# mcat-4cu-b-v2c.net
KiCad netlist of a schematic drawn in EAGLE
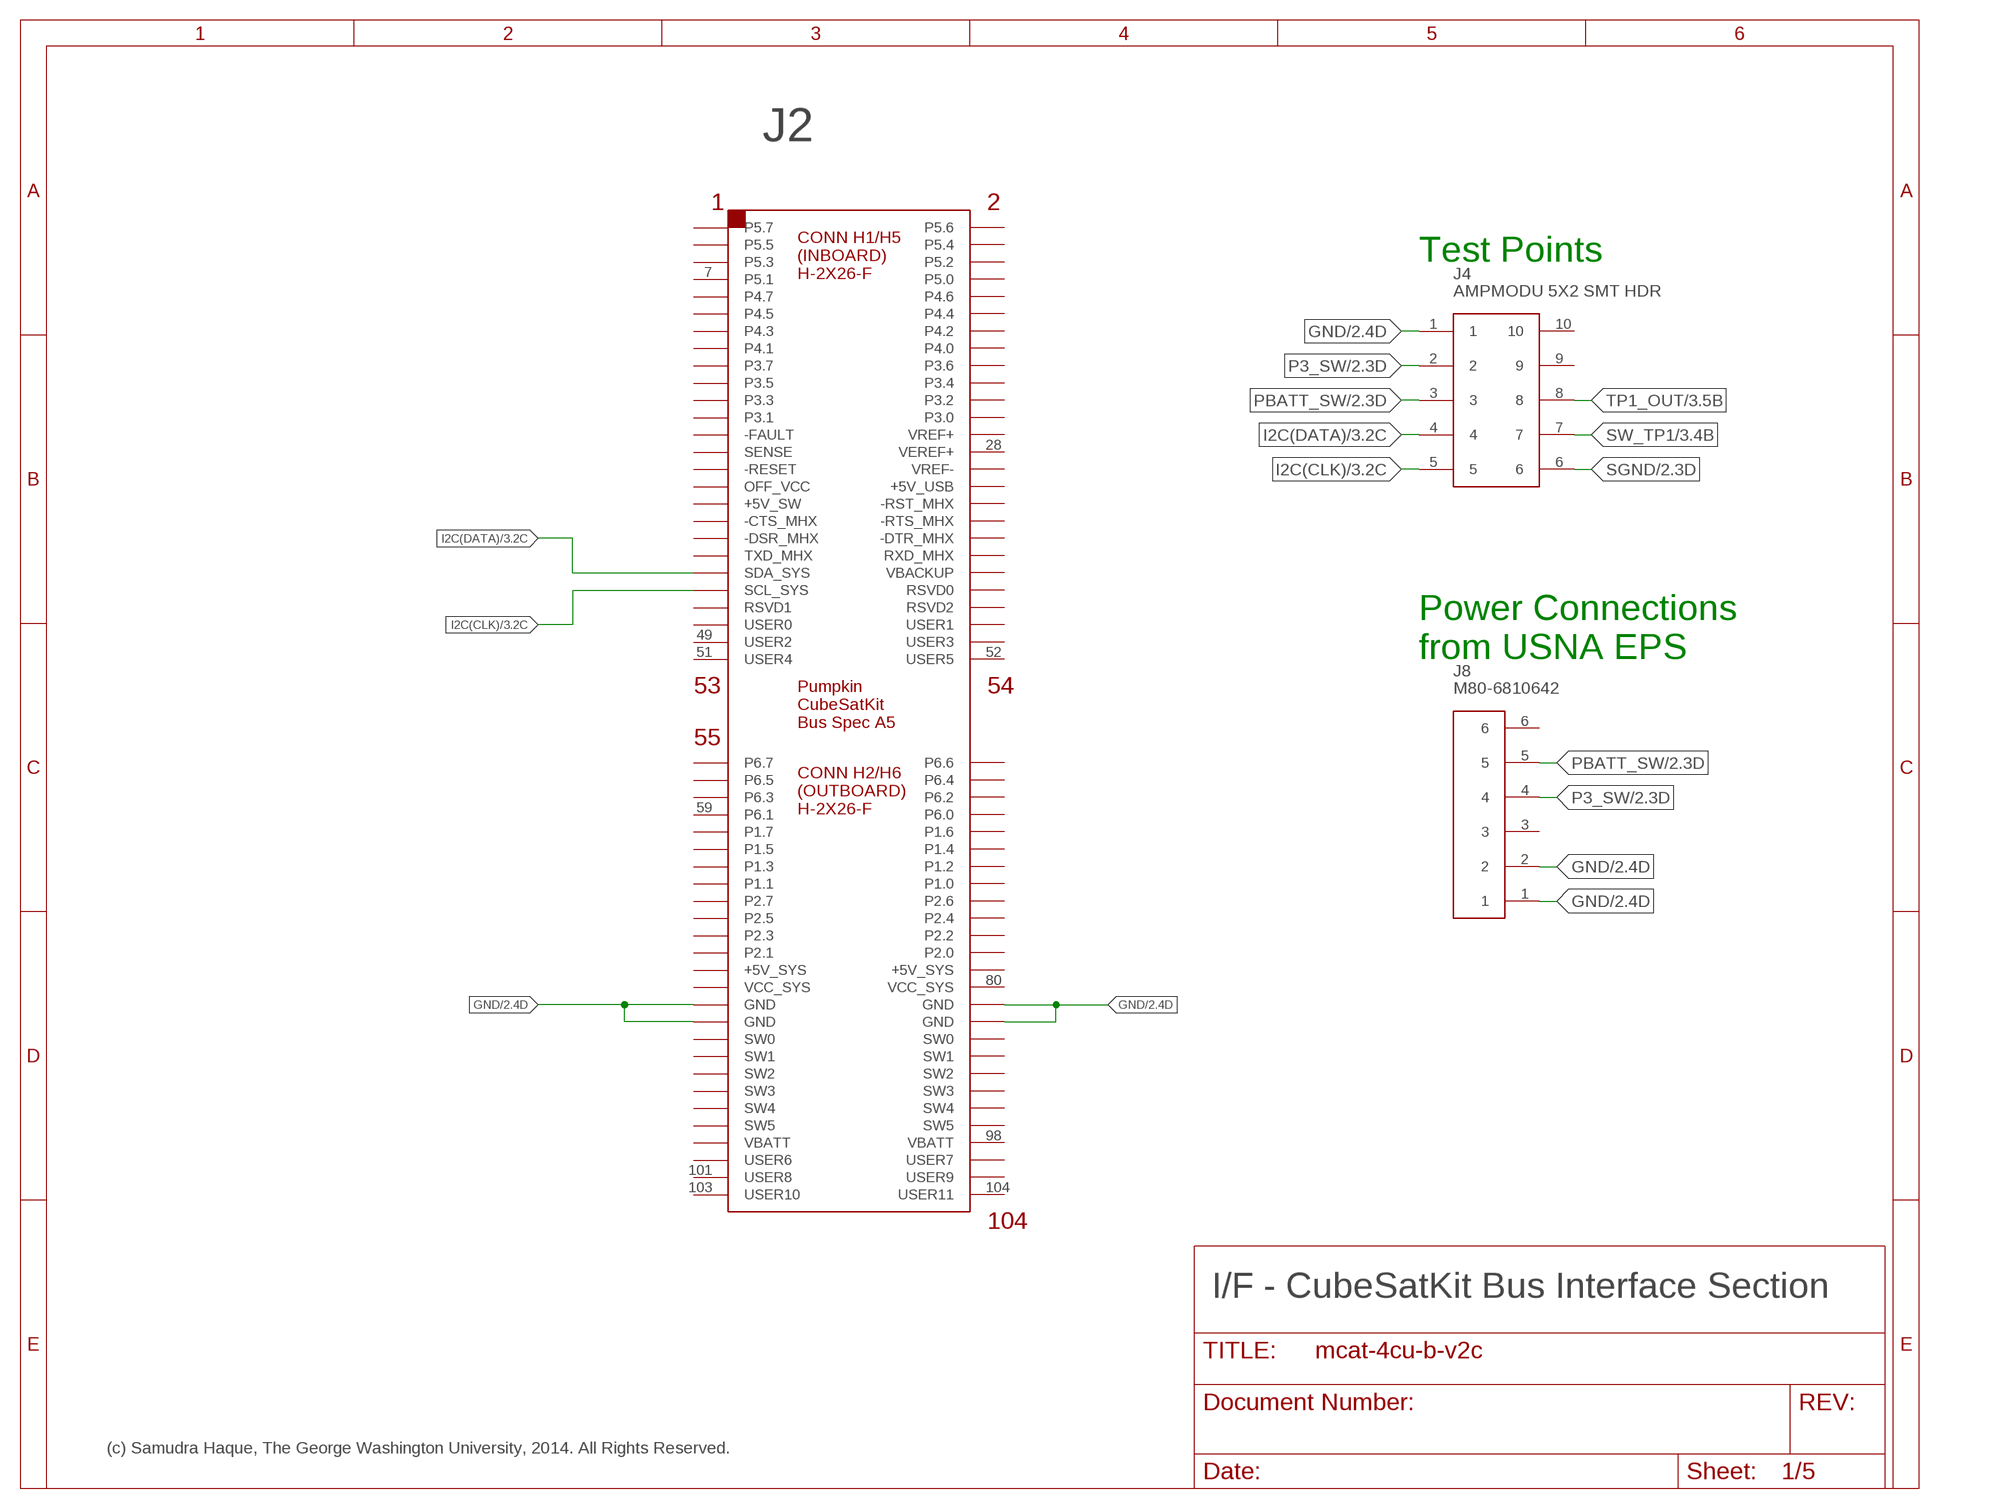
[diagram p0: schematic, sheet 1]
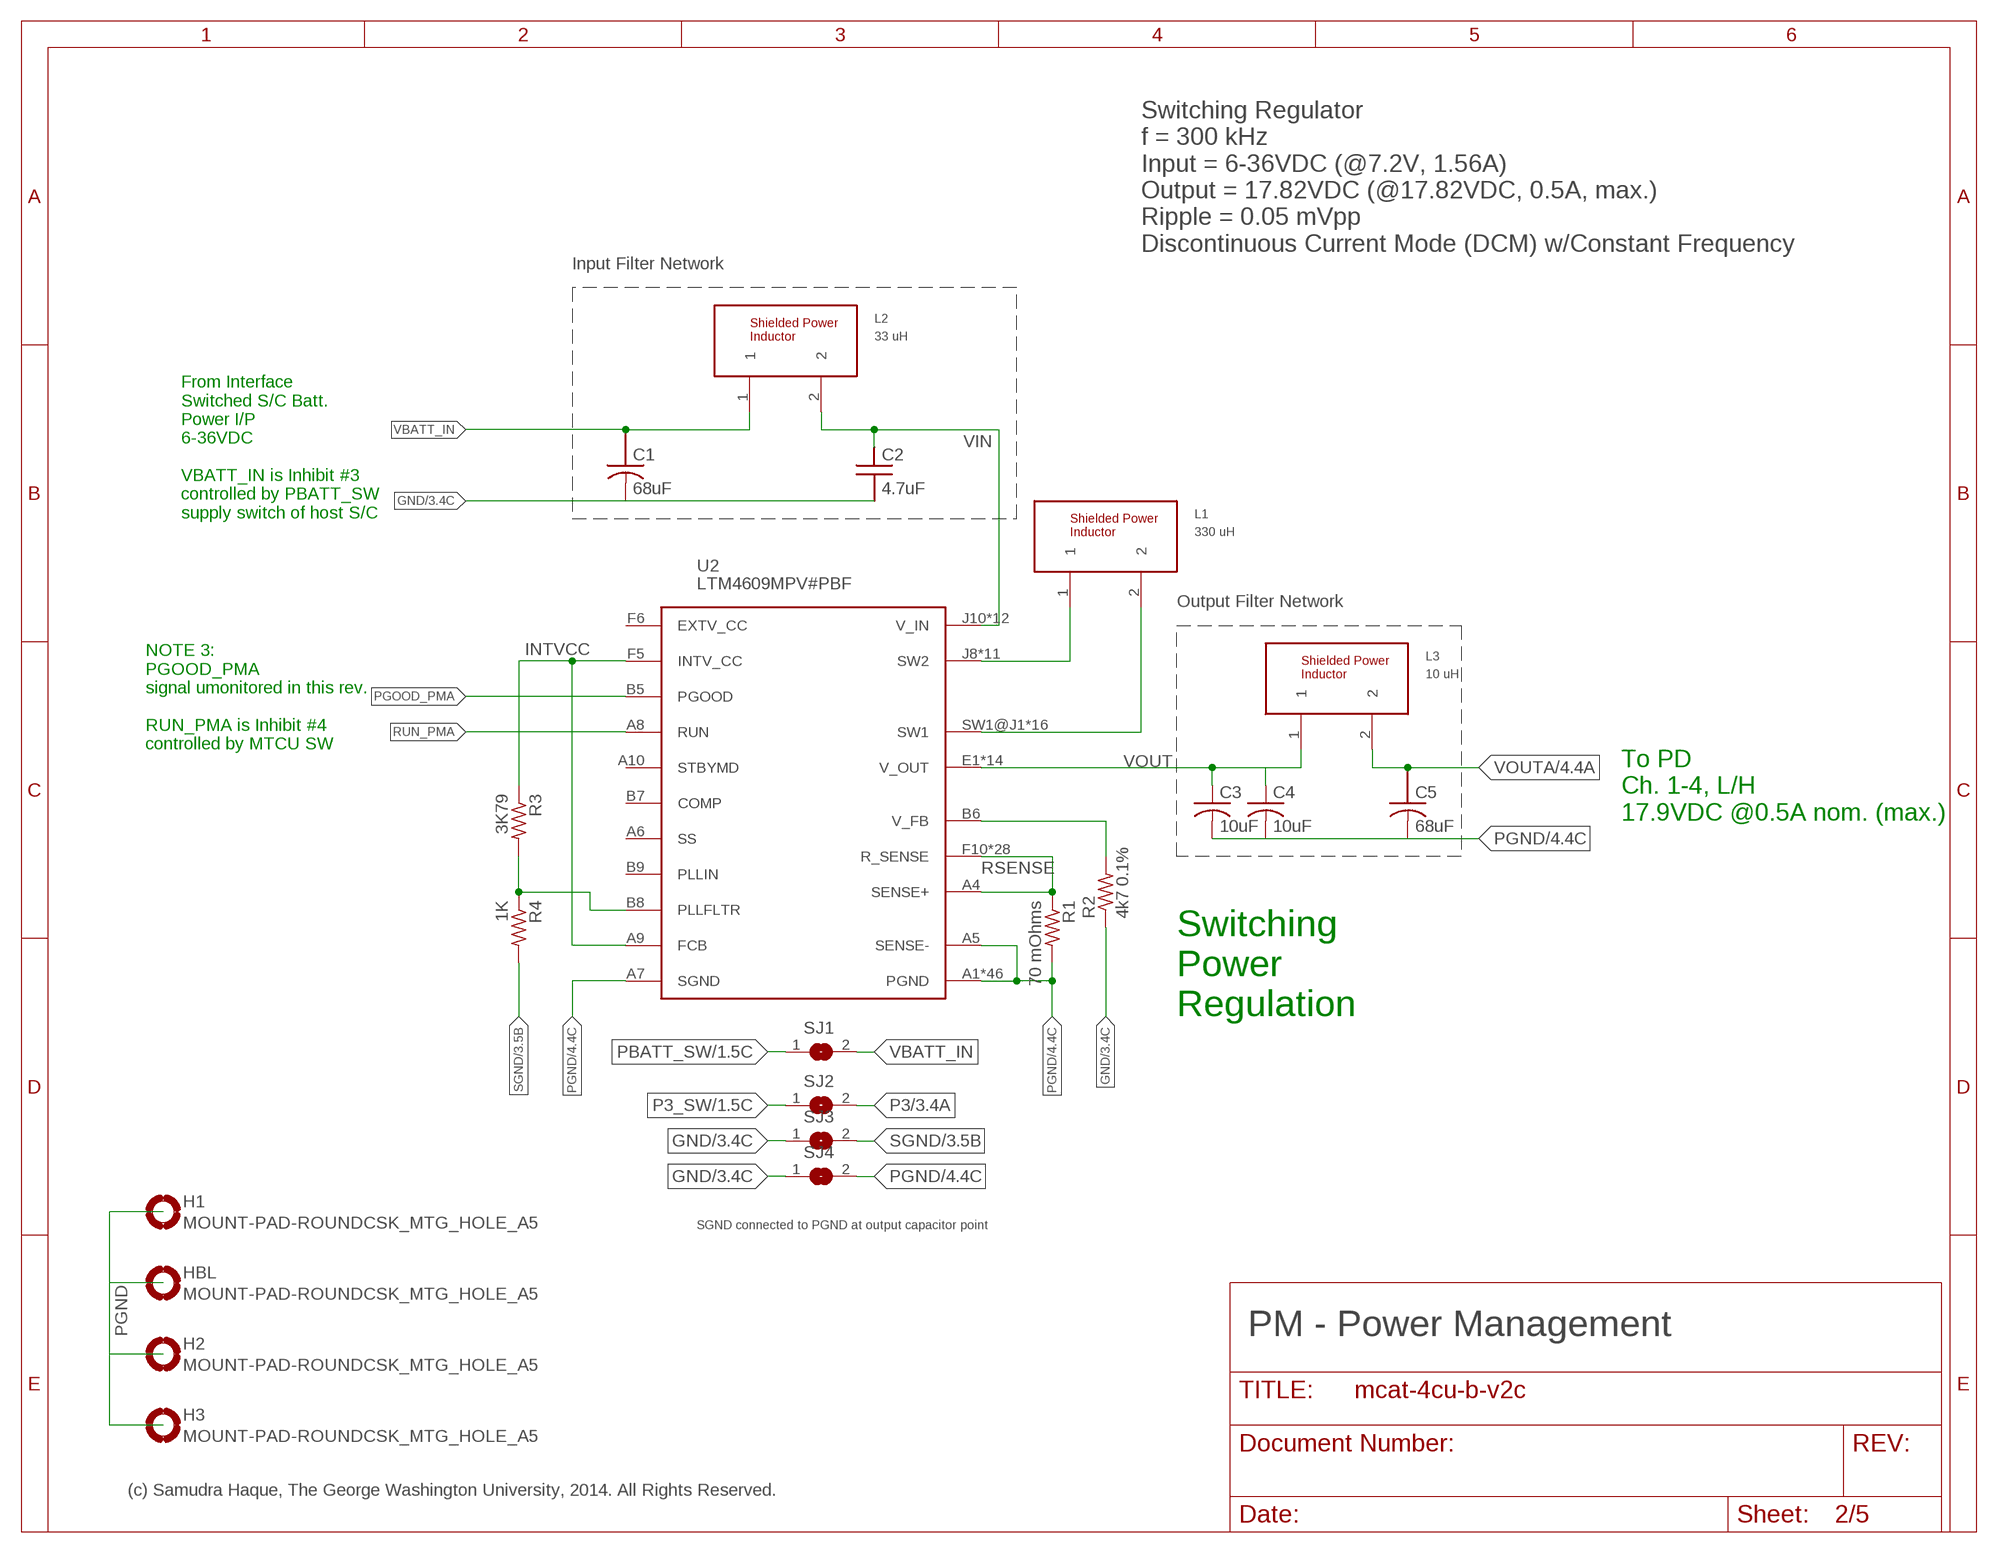
[diagram p1: schematic, sheet 2]
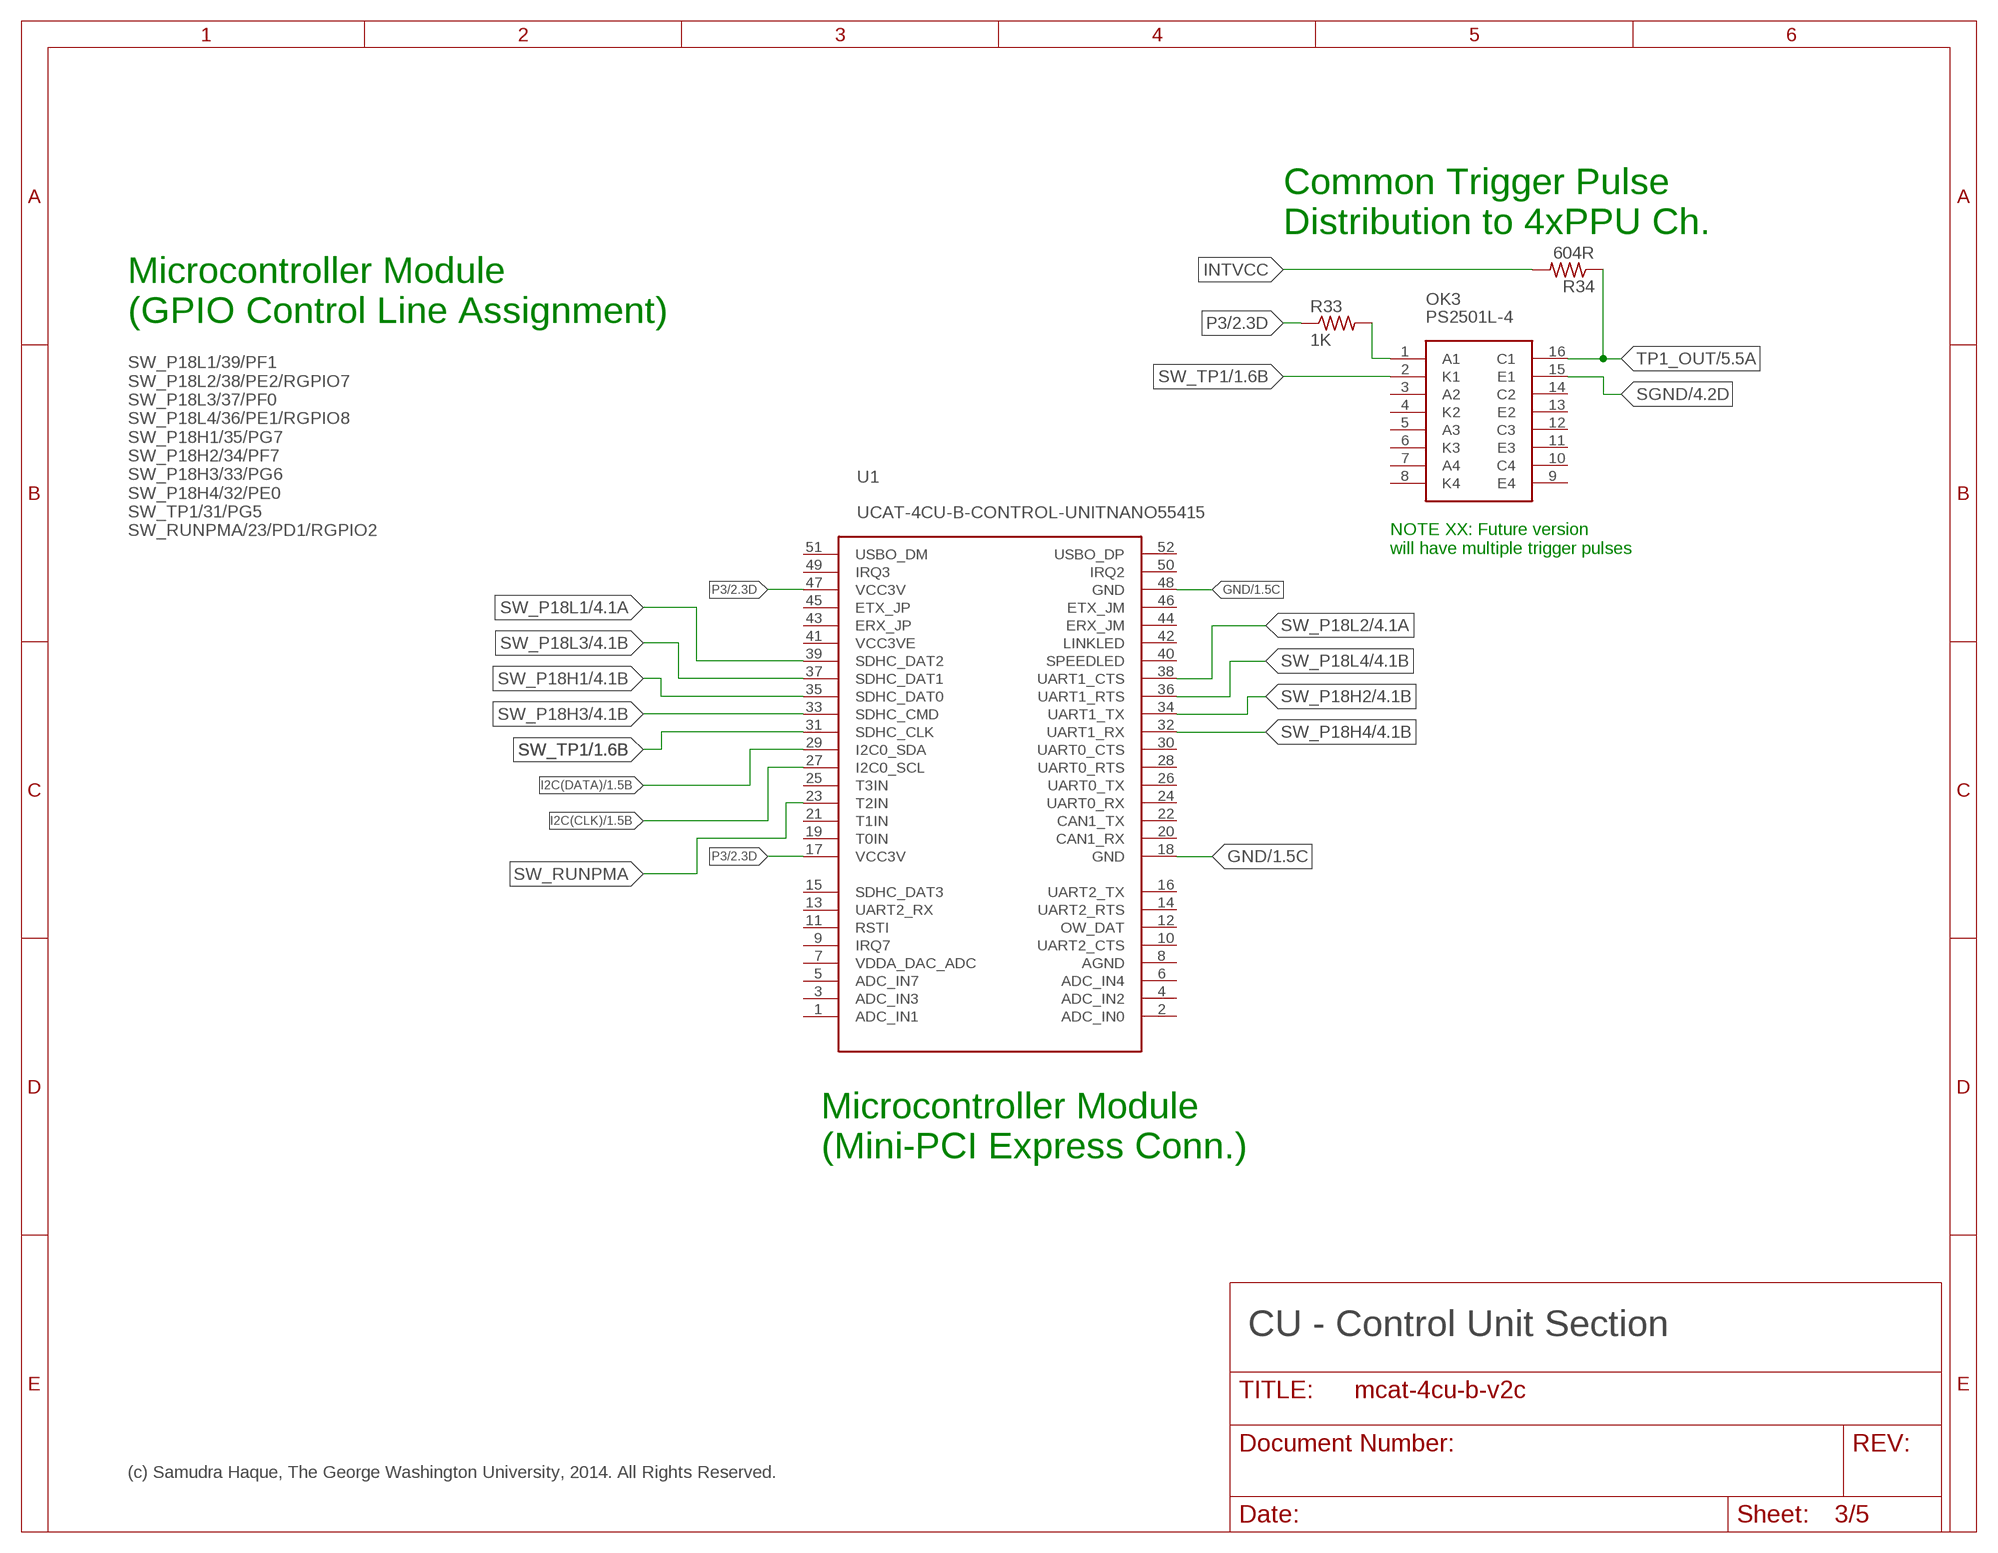
[diagram p2: schematic, sheet 3]
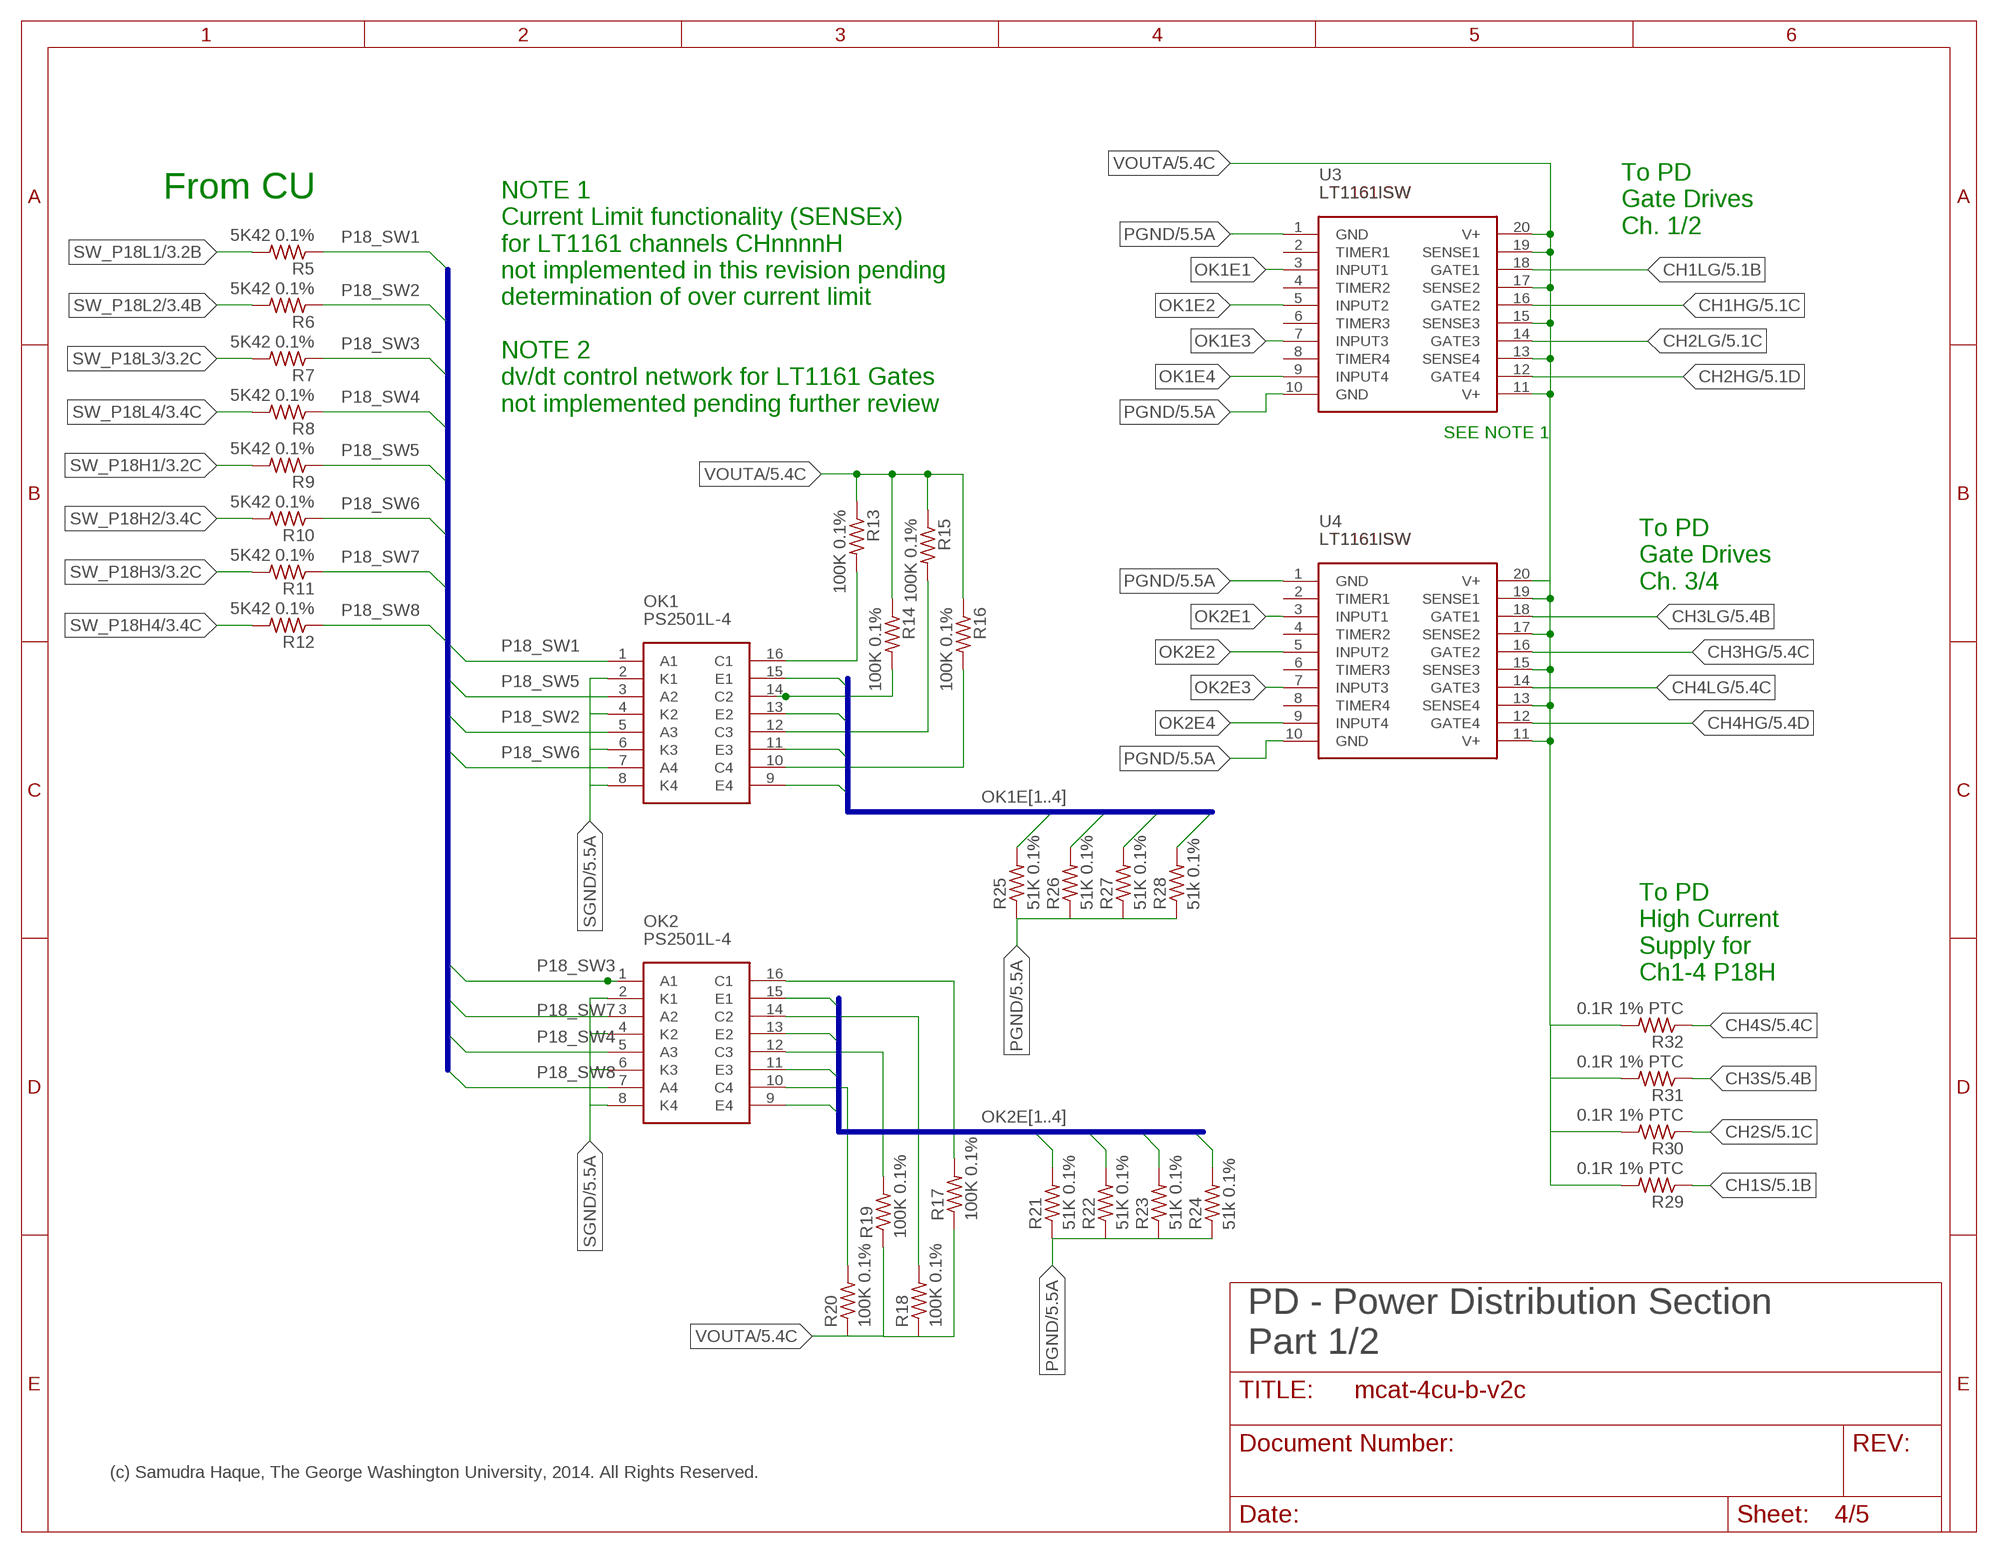
[diagram p3: schematic, sheet 4]
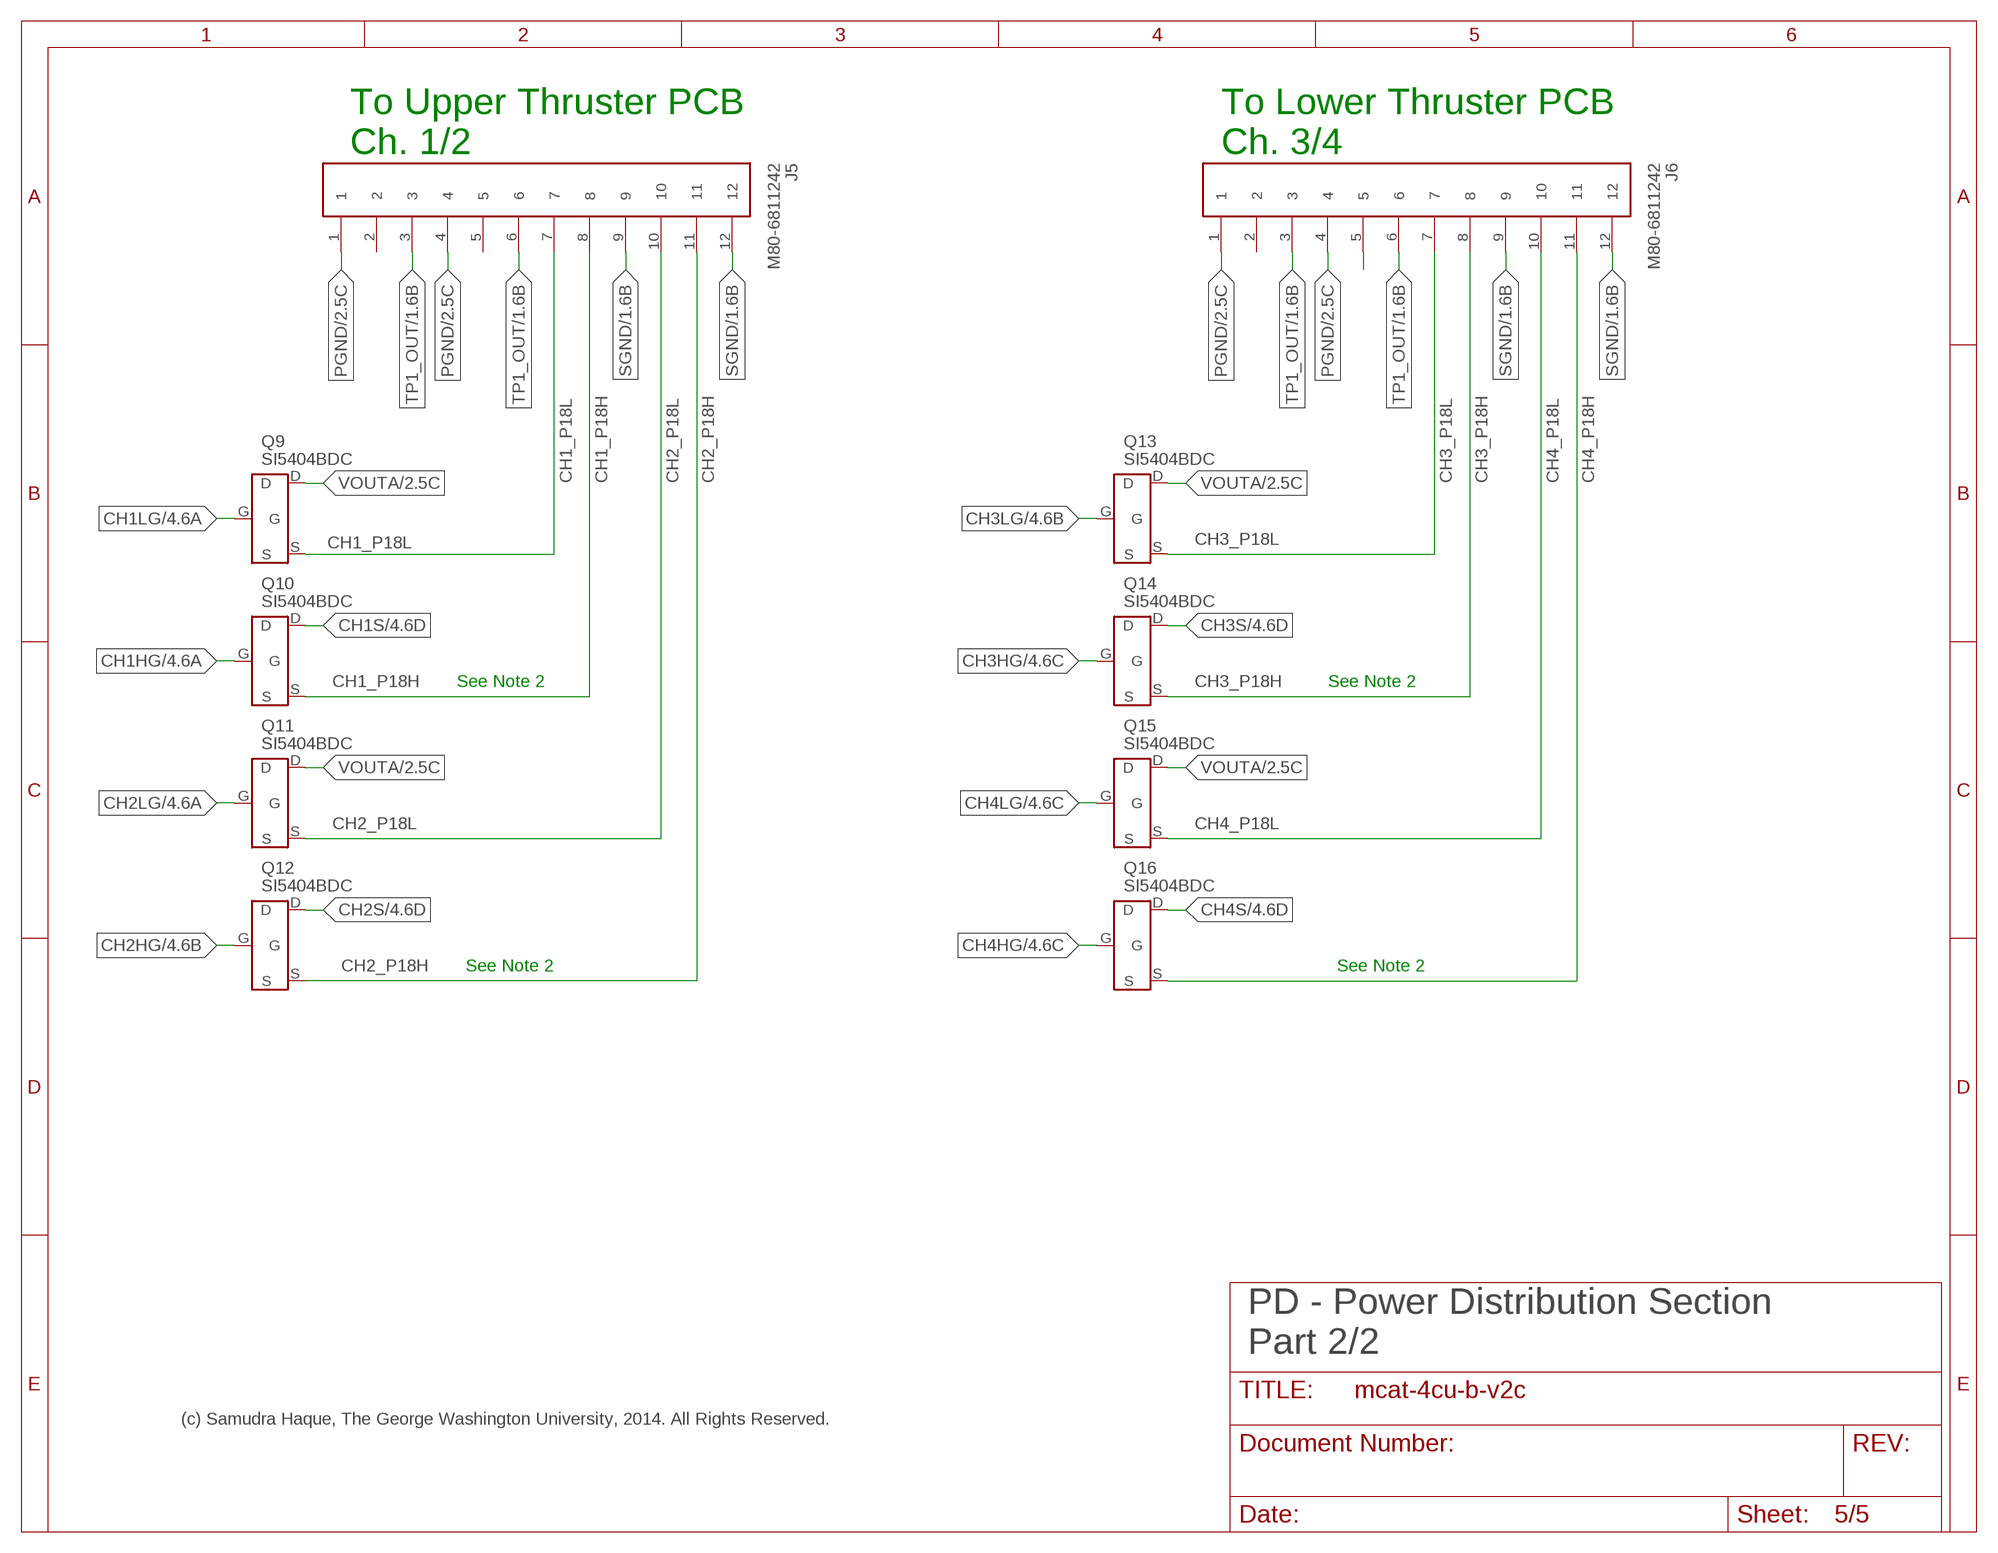
[diagram p4: schematic, sheet 5]

(export (version "E")
  (design (tool "Eeschema 10.0.6"))
  (components
    (comp (ref "OK1")
      (value "PS2501L-4")
      (footprint "eagle-import:PS2501L-4")
      (libsource (lib "eagle-import") (part "PS2501L-4"))
    )
    (comp (ref "OK2")
      (value "PS2501L-4")
      (footprint "eagle-import:PS2501L-4")
      (libsource (lib "eagle-import") (part "PS2501L-4"))
    )
    (comp (ref "R5")
      (value "5K42 0.1%")
      (footprint "eagle-import:R1206")
      (libsource (lib "eagle-import") (part "resistor_R-US_R1206"))
    )
    (comp (ref "R6")
      (value "5K42 0.1%")
      (footprint "eagle-import:R1206")
      (libsource (lib "eagle-import") (part "resistor_R-US_R1206"))
    )
    (comp (ref "R7")
      (value "5K42 0.1%")
      (footprint "eagle-import:R1206")
      (libsource (lib "eagle-import") (part "resistor_R-US_R1206"))
    )
    (comp (ref "R8")
      (value "5K42 0.1%")
      (footprint "eagle-import:R1206")
      (libsource (lib "eagle-import") (part "resistor_R-US_R1206"))
    )
    (comp (ref "R9")
      (value "5K42 0.1%")
      (footprint "eagle-import:R1206")
      (libsource (lib "eagle-import") (part "resistor_R-US_R1206"))
    )
    (comp (ref "R10")
      (value "5K42 0.1%")
      (footprint "eagle-import:R1206")
      (libsource (lib "eagle-import") (part "resistor_R-US_R1206"))
    )
    (comp (ref "R11")
      (value "5K42 0.1%")
      (footprint "eagle-import:R1206")
      (libsource (lib "eagle-import") (part "resistor_R-US_R1206"))
    )
    (comp (ref "R12")
      (value "5K42 0.1%")
      (footprint "eagle-import:R1206")
      (libsource (lib "eagle-import") (part "resistor_R-US_R1206"))
    )
    (comp (ref "R13")
      (value "100K 0.1%")
      (footprint "eagle-import:R0402")
      (libsource (lib "eagle-import") (part "resistor_R-US_R0402"))
    )
    (comp (ref "R14")
      (value "100K 0.1%")
      (footprint "eagle-import:R0402")
      (libsource (lib "eagle-import") (part "resistor_R-US_R0402"))
    )
    (comp (ref "R15")
      (value "100K 0.1%")
      (footprint "eagle-import:R0402")
      (libsource (lib "eagle-import") (part "resistor_R-US_R0402"))
    )
    (comp (ref "R16")
      (value "100K 0.1%")
      (footprint "eagle-import:R0402")
      (libsource (lib "eagle-import") (part "resistor_R-US_R0402"))
    )
    (comp (ref "R17")
      (value "100K 0.1%")
      (footprint "eagle-import:R0402")
      (libsource (lib "eagle-import") (part "resistor_R-US_R0402"))
    )
    (comp (ref "R18")
      (value "100K 0.1%")
      (footprint "eagle-import:R0402")
      (libsource (lib "eagle-import") (part "resistor_R-US_R0402"))
    )
    (comp (ref "R19")
      (value "100K 0.1%")
      (footprint "eagle-import:R0402")
      (libsource (lib "eagle-import") (part "resistor_R-US_R0402"))
    )
    (comp (ref "R20")
      (value "100K 0.1%")
      (footprint "eagle-import:R0402")
      (libsource (lib "eagle-import") (part "resistor_R-US_R0402"))
    )
    (comp (ref "R21")
      (value "51K 0.1%")
      (footprint "eagle-import:R0603")
      (libsource (lib "eagle-import") (part "resistor_R-US_R0603"))
    )
    (comp (ref "R22")
      (value "51K 0.1%")
      (footprint "eagle-import:R0603")
      (libsource (lib "eagle-import") (part "resistor_R-US_R0603"))
    )
    (comp (ref "R23")
      (value "51K 0.1%")
      (footprint "eagle-import:R0603")
      (libsource (lib "eagle-import") (part "resistor_R-US_R0603"))
    )
    (comp (ref "R24")
      (value "51k 0.1%")
      (footprint "eagle-import:R0603")
      (libsource (lib "eagle-import") (part "resistor_R-US_R0603"))
    )
    (comp (ref "R25")
      (value "51K 0.1%")
      (footprint "eagle-import:R0603")
      (libsource (lib "eagle-import") (part "resistor_R-US_R0603"))
    )
    (comp (ref "R26")
      (value "51K 0.1%")
      (footprint "eagle-import:R0603")
      (libsource (lib "eagle-import") (part "resistor_R-US_R0603"))
    )
    (comp (ref "R27")
      (value "51K 0.1%")
      (footprint "eagle-import:R0603")
      (libsource (lib "eagle-import") (part "resistor_R-US_R0603"))
    )
    (comp (ref "R28")
      (value "51k 0.1%")
      (footprint "eagle-import:R0603")
      (libsource (lib "eagle-import") (part "resistor_R-US_R0603"))
    )
    (comp (ref "R29")
      (value "0.1R 1% PTC")
      (footprint "eagle-import:R0402")
      (libsource (lib "eagle-import") (part "R-US_R0402"))
    )
    (comp (ref "R30")
      (value "0.1R 1% PTC")
      (footprint "eagle-import:R0402")
      (libsource (lib "eagle-import") (part "R-US_R0402"))
    )
    (comp (ref "R31")
      (value "0.1R 1% PTC")
      (footprint "eagle-import:R0402")
      (libsource (lib "eagle-import") (part "R-US_R0402"))
    )
    (comp (ref "R32")
      (value "0.1R 1% PTC")
      (footprint "eagle-import:R0402")
      (libsource (lib "eagle-import") (part "R-US_R0402"))
    )
    (comp (ref "U3")
      (value "LT1161ISW")
      (footprint "eagle-import:20-LEAD-PLASTIC-SO")
      (libsource (lib "eagle-import") (part "LT1161ISW"))
    )
    (comp (ref "U4")
      (value "LT1161ISW")
      (footprint "eagle-import:20-LEAD-PLASTIC-SO")
      (libsource (lib "eagle-import") (part "LT1161ISW"))
    )
    (comp (ref "J2")
      (value "CSK-BUS-CONN2X2X26")
      (footprint "eagle-import:CSK-BUS-PKG")
      (libsource (lib "eagle-import") (part "CSK-BUS-CONN2X2X26"))
    )
    (comp (ref "J4")
      (value "AMPMODU 5X2 SMT HDR")
      (footprint "eagle-import:AMPMODU-SMT-PIN-HEADER-5X2")
      (libsource (lib "eagle-import") (part "AMPMODU-5-146131-X(5X2)"))
    )
    (comp (ref "J8")
      (value "M80-6810642")
      (footprint "eagle-import:M80-68106")
      (libsource (lib "eagle-import") (part "M80-6810642"))
    )
    (comp (ref "OK3")
      (value "PS2501L-4")
      (footprint "eagle-import:PS2501L-4")
      (libsource (lib "eagle-import") (part "PS2501L-4"))
    )
    (comp (ref "R33")
      (value "1K")
      (footprint "eagle-import:R0805")
      (libsource (lib "eagle-import") (part "resistor_R-US_R0805"))
    )
    (comp (ref "R34")
      (value "604R")
      (footprint "eagle-import:R0805")
      (libsource (lib "eagle-import") (part "resistor_R-US_R0805"))
    )
    (comp (ref "U1")
      (value "UCAT-4CU-B-CONTROL-UNITNANO55415")
      (footprint "eagle-import:MOLEX-MINI-PCI-EXPRESS-8MM-52CKT")
      (libsource (lib "eagle-import") (part "UCAT-4CU-B-CONTROL-UNITNANO55415"))
    )
    (comp (ref "J5")
      (value "M80-6811242")
      (footprint "eagle-import:M80-68112")
      (libsource (lib "eagle-import") (part "M80-6811242"))
    )
    (comp (ref "J6")
      (value "M80-6811242")
      (footprint "eagle-import:M80-68112")
      (libsource (lib "eagle-import") (part "M80-6811242"))
    )
    (comp (ref "Q9")
      (value "SI5404BDC")
      (footprint "eagle-import:1206-8-CHIPFET")
      (libsource (lib "eagle-import") (part "SI5404BDC"))
    )
    (comp (ref "Q10")
      (value "SI5404BDC")
      (footprint "eagle-import:1206-8-CHIPFET")
      (libsource (lib "eagle-import") (part "SI5404BDC"))
    )
    (comp (ref "Q11")
      (value "SI5404BDC")
      (footprint "eagle-import:1206-8-CHIPFET")
      (libsource (lib "eagle-import") (part "SI5404BDC"))
    )
    (comp (ref "Q12")
      (value "SI5404BDC")
      (footprint "eagle-import:1206-8-CHIPFET")
      (libsource (lib "eagle-import") (part "SI5404BDC"))
    )
    (comp (ref "Q13")
      (value "SI5404BDC")
      (footprint "eagle-import:1206-8-CHIPFET")
      (libsource (lib "eagle-import") (part "SI5404BDC"))
    )
    (comp (ref "Q14")
      (value "SI5404BDC")
      (footprint "eagle-import:1206-8-CHIPFET")
      (libsource (lib "eagle-import") (part "SI5404BDC"))
    )
    (comp (ref "Q15")
      (value "SI5404BDC")
      (footprint "eagle-import:1206-8-CHIPFET")
      (libsource (lib "eagle-import") (part "SI5404BDC"))
    )
    (comp (ref "Q16")
      (value "SI5404BDC")
      (footprint "eagle-import:1206-8-CHIPFET")
      (libsource (lib "eagle-import") (part "SI5404BDC"))
    )
    (comp (ref "C1")
      (value "68uF")
      (footprint "eagle-import:OS-CON-SVPF-F12")
      (libsource (lib "eagle-import") (part "OSCON-50SVPF68M"))
    )
    (comp (ref "C2")
      (value "4.7uF")
      (footprint "eagle-import:MLCC-X7R-1210")
      (libsource (lib "eagle-import") (part "AVX-LD105C475KAB2A"))
    )
    (comp (ref "C3")
      (value "10uF")
      (footprint "eagle-import:C1210K")
      (libsource (lib "eagle-import") (part "C-USC1210K"))
    )
    (comp (ref "C4")
      (value "10uF")
      (footprint "eagle-import:C1210K")
      (libsource (lib "eagle-import") (part "C-USC1210K"))
    )
    (comp (ref "C5")
      (value "68uF")
      (footprint "eagle-import:OS-CON-SVPF-F12")
      (libsource (lib "eagle-import") (part "OSCON-50SVPF68M"))
    )
    (comp (ref "H1")
      (value "MOUNT-PAD-ROUNDCSK_MTG_HOLE_A5")
      (footprint "eagle-import:CSK_MOUNTING_HOLE")
      (libsource (lib "eagle-import") (part "MOUNT-PAD-ROUNDCSK_MTG_HOLE_A5"))
    )
    (comp (ref "H2")
      (value "MOUNT-PAD-ROUNDCSK_MTG_HOLE_A5")
      (footprint "eagle-import:CSK_MOUNTING_HOLE")
      (libsource (lib "eagle-import") (part "MOUNT-PAD-ROUNDCSK_MTG_HOLE_A5"))
    )
    (comp (ref "H3")
      (value "MOUNT-PAD-ROUNDCSK_MTG_HOLE_A5")
      (footprint "eagle-import:CSK_MOUNTING_HOLE")
      (libsource (lib "eagle-import") (part "MOUNT-PAD-ROUNDCSK_MTG_HOLE_A5"))
    )
    (comp (ref "HBL")
      (value "MOUNT-PAD-ROUNDCSK_MTG_HOLE_A5")
      (footprint "eagle-import:CSK_MOUNTING_HOLE")
      (libsource (lib "eagle-import") (part "MOUNT-PAD-ROUNDCSK_MTG_HOLE_A5"))
    )
    (comp (ref "L1")
      (value "330 uH")
      (footprint "eagle-import:MSS1048")
      (libsource (lib "eagle-import") (part "MSS1048-334KL_"))
    )
    (comp (ref "L2")
      (value "33 uH")
      (footprint "eagle-import:MSS1048")
      (libsource (lib "eagle-import") (part "MSS1038-333ML_"))
    )
    (comp (ref "L3")
      (value "10 uH")
      (footprint "eagle-import:SERIES-POWER-INDUCTORS")
      (fields (field (name "MF") "PANASONIC") (field (name "MPN") "ELL5PS100M"))
      (libsource (lib "eagle-import") (part "ELL-5PS100M"))
    )
    (comp (ref "R1")
      (value "70 mOhms")
      (footprint "eagle-import:R1206")
      (libsource (lib "eagle-import") (part "resistor_R-US_R1206"))
    )
    (comp (ref "R2")
      (value "4k7 0.1%")
      (footprint "eagle-import:R0603")
      (libsource (lib "eagle-import") (part "resistor_R-US_R0603"))
    )
    (comp (ref "R3")
      (value "3K79")
      (footprint "eagle-import:R0805")
      (libsource (lib "eagle-import") (part "R-US_R0805"))
    )
    (comp (ref "R4")
      (value "1K")
      (footprint "eagle-import:R0805")
      (libsource (lib "eagle-import") (part "R-US_R0805"))
    )
    (comp (ref "SJ1") (value "SJ") (footprint "eagle-import:SJ") (libsource (lib "eagle-import") (part "SJ")))
    (comp (ref "SJ2") (value "SJ") (footprint "eagle-import:SJ") (libsource (lib "eagle-import") (part "SJ")))
    (comp (ref "SJ3") (value "SJ") (footprint "eagle-import:SJ") (libsource (lib "eagle-import") (part "SJ")))
    (comp (ref "SJ4") (value "SJ") (footprint "eagle-import:SJ") (libsource (lib "eagle-import") (part "SJ")))
    (comp (ref "U2")
      (value "LTM4609MPV#PBF")
      (footprint "eagle-import:LGA-141-LTC-05-08-1840-B")
      (libsource (lib "eagle-import") (part "LTM4609MPV#PBFROHS/HITEMP"))
    )
  )
  (nets
    (net (code "3") (name "CH1HG") (class "Default")
      (node (ref "Q10") (pin "G") (pinfunction "G_G") (pintype "bidirectional"))
      (node (ref "U3") (pin "16") (pinfunction "GATE2_16") (pintype "bidirectional"))
    )
    (net (code "4") (name "CH1LG") (class "Default")
      (node (ref "Q9") (pin "G") (pinfunction "G_G") (pintype "bidirectional"))
      (node (ref "U3") (pin "18") (pinfunction "GATE1_18") (pintype "bidirectional"))
    )
    (net (code "5") (name "CH1S") (class "Default")
      (node (ref "Q10") (pin "D") (pinfunction "D_D") (pintype "bidirectional"))
      (node (ref "R29") (pin "1") (pinfunction "1_1") (pintype "passive"))
    )
    (net (code "6") (name "CH1_P18H") (class "Default")
      (node (ref "J5") (pin "8") (pinfunction "8_8") (pintype "bidirectional"))
      (node (ref "Q10") (pin "S") (pinfunction "S_S") (pintype "bidirectional"))
    )
    (net (code "7") (name "CH1_P18L") (class "Default")
      (node (ref "J5") (pin "7") (pinfunction "7_7") (pintype "bidirectional"))
      (node (ref "Q9") (pin "S") (pinfunction "S_S") (pintype "bidirectional"))
    )
    (net (code "8") (name "CH2HG") (class "Default")
      (node (ref "Q12") (pin "G") (pinfunction "G_G") (pintype "bidirectional"))
      (node (ref "U3") (pin "12") (pinfunction "GATE4_12") (pintype "bidirectional"))
    )
    (net (code "9") (name "CH2LG") (class "Default")
      (node (ref "Q11") (pin "G") (pinfunction "G_G") (pintype "bidirectional"))
      (node (ref "U3") (pin "14") (pinfunction "GATE3_14") (pintype "bidirectional"))
    )
    (net (code "10") (name "CH2S") (class "Default")
      (node (ref "Q12") (pin "D") (pinfunction "D_D") (pintype "bidirectional"))
      (node (ref "R30") (pin "1") (pinfunction "1_1") (pintype "passive"))
    )
    (net (code "11") (name "CH2_P18H") (class "Default")
      (node (ref "J5") (pin "11") (pinfunction "11_11") (pintype "bidirectional"))
      (node (ref "Q12") (pin "S") (pinfunction "S_S") (pintype "bidirectional"))
    )
    (net (code "12") (name "CH2_P18L") (class "Default")
      (node (ref "J5") (pin "10") (pinfunction "10_10") (pintype "bidirectional"))
      (node (ref "Q11") (pin "S") (pinfunction "S_S") (pintype "bidirectional"))
    )
    (net (code "13") (name "CH3HG") (class "Default")
      (node (ref "Q14") (pin "G") (pinfunction "G_G") (pintype "bidirectional"))
      (node (ref "U4") (pin "16") (pinfunction "GATE2_16") (pintype "bidirectional"))
    )
    (net (code "14") (name "CH3LG") (class "Default")
      (node (ref "Q13") (pin "G") (pinfunction "G_G") (pintype "bidirectional"))
      (node (ref "U4") (pin "18") (pinfunction "GATE1_18") (pintype "bidirectional"))
    )
    (net (code "15") (name "CH3S") (class "Default")
      (node (ref "Q14") (pin "D") (pinfunction "D_D") (pintype "bidirectional"))
      (node (ref "R31") (pin "1") (pinfunction "1_1") (pintype "passive"))
    )
    (net (code "16") (name "CH3_P18H") (class "Default")
      (node (ref "J6") (pin "8") (pinfunction "8_8") (pintype "bidirectional"))
      (node (ref "Q14") (pin "S") (pinfunction "S_S") (pintype "bidirectional"))
    )
    (net (code "17") (name "CH3_P18L") (class "Default")
      (node (ref "J6") (pin "7") (pinfunction "7_7") (pintype "bidirectional"))
      (node (ref "Q13") (pin "S") (pinfunction "S_S") (pintype "bidirectional"))
    )
    (net (code "18") (name "CH4HG") (class "Default")
      (node (ref "Q16") (pin "G") (pinfunction "G_G") (pintype "bidirectional"))
      (node (ref "U4") (pin "12") (pinfunction "GATE4_12") (pintype "bidirectional"))
    )
    (net (code "19") (name "CH4LG") (class "Default")
      (node (ref "Q15") (pin "G") (pinfunction "G_G") (pintype "bidirectional"))
      (node (ref "U4") (pin "14") (pinfunction "GATE3_14") (pintype "bidirectional"))
    )
    (net (code "20") (name "CH4S") (class "Default")
      (node (ref "Q16") (pin "D") (pinfunction "D_D") (pintype "bidirectional"))
      (node (ref "R32") (pin "1") (pinfunction "1_1") (pintype "passive"))
    )
    (net (code "21") (name "CH4_P18H") (class "Default")
      (node (ref "J6") (pin "11") (pinfunction "11_11") (pintype "bidirectional"))
      (node (ref "Q16") (pin "S") (pinfunction "S_S") (pintype "bidirectional"))
    )
    (net (code "22") (name "CH4_P18L") (class "Default")
      (node (ref "J6") (pin "10") (pinfunction "10_10") (pintype "bidirectional"))
      (node (ref "Q15") (pin "S") (pinfunction "S_S") (pintype "bidirectional"))
    )
    (net (code "23") (name "GND") (class "Default")
      (node (ref "C1") (pin "K1") (pinfunction "K_K1") (pintype "passive"))
      (node (ref "C2") (pin "2") (pinfunction "2_2") (pintype "passive"))
      (node (ref "J2") (pin "81") (pinfunction "GND_81") (pintype "bidirectional"))
      (node (ref "J2") (pin "82") (pinfunction "GND_82") (pintype "bidirectional"))
      (node (ref "J2") (pin "83") (pinfunction "GND_83") (pintype "bidirectional"))
      (node (ref "J2") (pin "84") (pinfunction "GND_84") (pintype "bidirectional"))
      (node (ref "J4") (pin "1") (pinfunction "1_1") (pintype "bidirectional"))
      (node (ref "J8") (pin "1") (pinfunction "1_1") (pintype "bidirectional"))
      (node (ref "J8") (pin "2") (pinfunction "2_2") (pintype "bidirectional"))
      (node (ref "R2") (pin "1") (pinfunction "1_1") (pintype "passive"))
      (node (ref "SJ3") (pin "1") (pinfunction "1_1") (pintype "passive"))
      (node (ref "SJ4") (pin "1") (pinfunction "1_1") (pintype "passive"))
      (node (ref "U1") (pin "18") (pinfunction "GND_18") (pintype "bidirectional"))
      (node (ref "U1") (pin "48") (pinfunction "GND_48") (pintype "bidirectional"))
    )
    (net (code "24") (name "I2C(CLK)") (class "Default")
      (node (ref "J2") (pin "43") (pinfunction "SCL_SYS_43") (pintype "bidirectional"))
      (node (ref "J4") (pin "5") (pinfunction "5_5") (pintype "bidirectional"))
      (node (ref "U1") (pin "27") (pinfunction "I2C0_SCL_27") (pintype "bidirectional"))
    )
    (net (code "25") (name "I2C(DATA)") (class "Default")
      (node (ref "J2") (pin "41") (pinfunction "SDA_SYS_41") (pintype "bidirectional"))
      (node (ref "J4") (pin "4") (pinfunction "4_4") (pintype "bidirectional"))
      (node (ref "U1") (pin "29") (pinfunction "I2C0_SDA_29") (pintype "bidirectional"))
    )
    (net (code "26") (name "INTVCC") (class "Default")
      (node (ref "R3") (pin "1") (pinfunction "1_1") (pintype "passive"))
      (node (ref "R34") (pin "2") (pinfunction "2_2") (pintype "passive"))
      (node (ref "U2") (pin "A9") (pinfunction "FCB_A9") (pintype "bidirectional"))
      (node (ref "U2") (pin "F5") (pinfunction "INTV_CC_F5") (pintype "bidirectional"))
    )
    (net (code "27") (name "Net-(L1-Pad1)") (class "Default")
      (node (ref "L1") (pin "1") (pinfunction "1_1") (pintype "bidirectional"))
      (node (ref "U2") (pin "J8") (pinfunction "SW2_J8") (pintype "bidirectional"))
      (node (ref "U2") (pin "J9") (pinfunction "SW2_J9") (pintype "bidirectional"))
      (node (ref "U2") (pin "K7") (pinfunction "SW2_K7") (pintype "bidirectional"))
      (node (ref "U2") (pin "K8") (pinfunction "SW2_K8") (pintype "bidirectional"))
      (node (ref "U2") (pin "K9") (pinfunction "SW2_K9") (pintype "bidirectional"))
      (node (ref "U2") (pin "L7") (pinfunction "SW2_L7") (pintype "bidirectional"))
      (node (ref "U2") (pin "L8") (pinfunction "SW2_L8") (pintype "bidirectional"))
      (node (ref "U2") (pin "L9") (pinfunction "SW2_L9") (pintype "bidirectional"))
      (node (ref "U2") (pin "M7") (pinfunction "SW2_M7") (pintype "bidirectional"))
      (node (ref "U2") (pin "M8") (pinfunction "SW2_M8") (pintype "bidirectional"))
      (node (ref "U2") (pin "M9") (pinfunction "SW2_M9") (pintype "bidirectional"))
    )
    (net (code "28") (name "Net-(L1-Pad2)") (class "Default")
      (node (ref "L1") (pin "2") (pinfunction "2_2") (pintype "bidirectional"))
      (node (ref "U2") (pin "SW1@J1") (pinfunction "SW1_SW1@J1") (pintype "bidirectional"))
      (node (ref "U2") (pin "SW1@J2") (pinfunction "SW1_SW1@J2") (pintype "bidirectional"))
      (node (ref "U2") (pin "SW1@J3") (pinfunction "SW1_SW1@J3") (pintype "bidirectional"))
      (node (ref "U2") (pin "SW1@J4") (pinfunction "SW1_SW1@J4") (pintype "bidirectional"))
      (node (ref "U2") (pin "SW1@K1") (pinfunction "SW1_SW1@K1") (pintype "bidirectional"))
      (node (ref "U2") (pin "SW1@K2") (pinfunction "SW1_SW1@K2") (pintype "bidirectional"))
      (node (ref "U2") (pin "SW1@K3") (pinfunction "SW1_SW1@K3") (pintype "bidirectional"))
      (node (ref "U2") (pin "SW1@K4") (pinfunction "SW1_SW1@K4") (pintype "bidirectional"))
      (node (ref "U2") (pin "SW1@L1") (pinfunction "SW1_SW1@L1") (pintype "bidirectional"))
      (node (ref "U2") (pin "SW1@L2") (pinfunction "SW1_SW1@L2") (pintype "bidirectional"))
      (node (ref "U2") (pin "SW1@L3") (pinfunction "SW1_SW1@L3") (pintype "bidirectional"))
      (node (ref "U2") (pin "SW1@L4") (pinfunction "SW1_SW1@L4") (pintype "bidirectional"))
      (node (ref "U2") (pin "SW1@M1") (pinfunction "SW1_SW1@M1") (pintype "bidirectional"))
      (node (ref "U2") (pin "SW1@M2") (pinfunction "SW1_SW1@M2") (pintype "bidirectional"))
      (node (ref "U2") (pin "SW1@M3") (pinfunction "SW1_SW1@M3") (pintype "bidirectional"))
      (node (ref "U2") (pin "SW1@M4") (pinfunction "SW1_SW1@M4") (pintype "bidirectional"))
    )
    (net (code "29") (name "Net-(OK1-C1)") (class "Default")
      (node (ref "OK1") (pin "16") (pinfunction "C1_16") (pintype "bidirectional"))
      (node (ref "R13") (pin "2") (pinfunction "2_2") (pintype "passive"))
    )
    (net (code "30") (name "Net-(OK1-C2)") (class "Default")
      (node (ref "OK1") (pin "14") (pinfunction "C2_14") (pintype "bidirectional"))
      (node (ref "R14") (pin "2") (pinfunction "2_2") (pintype "passive"))
    )
    (net (code "31") (name "Net-(OK1-C3)") (class "Default")
      (node (ref "OK1") (pin "12") (pinfunction "C3_12") (pintype "bidirectional"))
      (node (ref "R15") (pin "2") (pinfunction "2_2") (pintype "passive"))
    )
    (net (code "32") (name "Net-(OK1-C4)") (class "Default")
      (node (ref "OK1") (pin "10") (pinfunction "C4_10") (pintype "bidirectional"))
      (node (ref "R16") (pin "2") (pinfunction "2_2") (pintype "passive"))
    )
    (net (code "33") (name "Net-(OK2-C1)") (class "Default")
      (node (ref "OK2") (pin "16") (pinfunction "C1_16") (pintype "bidirectional"))
      (node (ref "R17") (pin "2") (pinfunction "2_2") (pintype "passive"))
    )
    (net (code "34") (name "Net-(OK2-C2)") (class "Default")
      (node (ref "OK2") (pin "14") (pinfunction "C2_14") (pintype "bidirectional"))
      (node (ref "R18") (pin "2") (pinfunction "2_2") (pintype "passive"))
    )
    (net (code "35") (name "Net-(OK2-C3)") (class "Default")
      (node (ref "OK2") (pin "12") (pinfunction "C3_12") (pintype "bidirectional"))
      (node (ref "R19") (pin "2") (pinfunction "2_2") (pintype "passive"))
    )
    (net (code "36") (name "Net-(OK2-C4)") (class "Default")
      (node (ref "OK2") (pin "10") (pinfunction "C4_10") (pintype "bidirectional"))
      (node (ref "R20") (pin "2") (pinfunction "2_2") (pintype "passive"))
    )
    (net (code "37") (name "Net-(OK3-A1)") (class "Default")
      (node (ref "OK3") (pin "1") (pinfunction "A1_1") (pintype "bidirectional"))
      (node (ref "R33") (pin "2") (pinfunction "2_2") (pintype "passive"))
    )
    (net (code "38") (name "Net-(U2-PLLFLTR)") (class "Default")
      (node (ref "R3") (pin "2") (pinfunction "2_2") (pintype "passive"))
      (node (ref "R4") (pin "1") (pinfunction "1_1") (pintype "passive"))
      (node (ref "U2") (pin "B8") (pinfunction "PLLFLTR_B8") (pintype "bidirectional"))
    )
    (net (code "39") (name "Net-(U2-V_FB)") (class "Default")
      (node (ref "R2") (pin "2") (pinfunction "2_2") (pintype "passive"))
      (node (ref "U2") (pin "B6") (pinfunction "V_FB_B6") (pintype "bidirectional"))
    )
    (net (code "40") (name "OK1E1") (class "Default")
      (node (ref "OK1") (pin "15") (pinfunction "E1_15") (pintype "bidirectional"))
      (node (ref "R25") (pin "2") (pinfunction "2_2") (pintype "passive"))
      (node (ref "U3") (pin "3") (pinfunction "INPUT1_3") (pintype "bidirectional"))
    )
    (net (code "41") (name "OK1E2") (class "Default")
      (node (ref "OK1") (pin "13") (pinfunction "E2_13") (pintype "bidirectional"))
      (node (ref "R26") (pin "2") (pinfunction "2_2") (pintype "passive"))
      (node (ref "U3") (pin "5") (pinfunction "INPUT2_5") (pintype "bidirectional"))
    )
    (net (code "42") (name "OK1E3") (class "Default")
      (node (ref "OK1") (pin "11") (pinfunction "E3_11") (pintype "bidirectional"))
      (node (ref "R27") (pin "2") (pinfunction "2_2") (pintype "passive"))
      (node (ref "U3") (pin "7") (pinfunction "INPUT3_7") (pintype "bidirectional"))
    )
    (net (code "43") (name "OK1E4") (class "Default")
      (node (ref "OK1") (pin "9") (pinfunction "E4_9") (pintype "bidirectional"))
      (node (ref "R28") (pin "2") (pinfunction "2_2") (pintype "passive"))
      (node (ref "U3") (pin "9") (pinfunction "INPUT4_9") (pintype "bidirectional"))
    )
    (net (code "44") (name "OK2E1") (class "Default")
      (node (ref "OK2") (pin "15") (pinfunction "E1_15") (pintype "bidirectional"))
      (node (ref "R21") (pin "2") (pinfunction "2_2") (pintype "passive"))
      (node (ref "U4") (pin "3") (pinfunction "INPUT1_3") (pintype "bidirectional"))
    )
    (net (code "45") (name "OK2E2") (class "Default")
      (node (ref "OK2") (pin "13") (pinfunction "E2_13") (pintype "bidirectional"))
      (node (ref "R22") (pin "2") (pinfunction "2_2") (pintype "passive"))
      (node (ref "U4") (pin "5") (pinfunction "INPUT2_5") (pintype "bidirectional"))
    )
    (net (code "46") (name "OK2E3") (class "Default")
      (node (ref "OK2") (pin "11") (pinfunction "E3_11") (pintype "bidirectional"))
      (node (ref "R23") (pin "2") (pinfunction "2_2") (pintype "passive"))
      (node (ref "U4") (pin "7") (pinfunction "INPUT3_7") (pintype "bidirectional"))
    )
    (net (code "47") (name "OK2E4") (class "Default")
      (node (ref "OK2") (pin "9") (pinfunction "E4_9") (pintype "bidirectional"))
      (node (ref "R24") (pin "2") (pinfunction "2_2") (pintype "passive"))
      (node (ref "U4") (pin "9") (pinfunction "INPUT4_9") (pintype "bidirectional"))
    )
    (net (code "48") (name "P3") (class "Default")
      (node (ref "R33") (pin "1") (pinfunction "1_1") (pintype "passive"))
      (node (ref "SJ2") (pin "2") (pinfunction "2_2") (pintype "passive"))
      (node (ref "U1") (pin "17") (pinfunction "VCC3V_17") (pintype "bidirectional"))
      (node (ref "U1") (pin "47") (pinfunction "VCC3V_47") (pintype "bidirectional"))
    )
    (net (code "49") (name "P3_SW") (class "Default")
      (node (ref "J4") (pin "2") (pinfunction "2_2") (pintype "bidirectional"))
      (node (ref "J8") (pin "4") (pinfunction "4_4") (pintype "bidirectional"))
      (node (ref "SJ2") (pin "1") (pinfunction "1_1") (pintype "passive"))
    )
    (net (code "50") (name "P18_SW1") (class "Default")
      (node (ref "OK1") (pin "1") (pinfunction "A1_1") (pintype "bidirectional"))
      (node (ref "R5") (pin "1") (pinfunction "1_1") (pintype "passive"))
    )
    (net (code "51") (name "P18_SW2") (class "Default")
      (node (ref "OK1") (pin "5") (pinfunction "A3_5") (pintype "bidirectional"))
      (node (ref "R6") (pin "1") (pinfunction "1_1") (pintype "passive"))
    )
    (net (code "52") (name "P18_SW3") (class "Default")
      (node (ref "OK2") (pin "1") (pinfunction "A1_1") (pintype "bidirectional"))
      (node (ref "R7") (pin "1") (pinfunction "1_1") (pintype "passive"))
    )
    (net (code "53") (name "P18_SW4") (class "Default")
      (node (ref "OK2") (pin "5") (pinfunction "A3_5") (pintype "bidirectional"))
      (node (ref "R8") (pin "1") (pinfunction "1_1") (pintype "passive"))
    )
    (net (code "54") (name "P18_SW5") (class "Default")
      (node (ref "OK1") (pin "3") (pinfunction "A2_3") (pintype "bidirectional"))
      (node (ref "R9") (pin "1") (pinfunction "1_1") (pintype "passive"))
    )
    (net (code "55") (name "P18_SW6") (class "Default")
      (node (ref "OK1") (pin "7") (pinfunction "A4_7") (pintype "bidirectional"))
      (node (ref "R10") (pin "1") (pinfunction "1_1") (pintype "passive"))
    )
    (net (code "56") (name "P18_SW7") (class "Default")
      (node (ref "OK2") (pin "3") (pinfunction "A2_3") (pintype "bidirectional"))
      (node (ref "R11") (pin "1") (pinfunction "1_1") (pintype "passive"))
    )
    (net (code "57") (name "P18_SW8") (class "Default")
      (node (ref "OK2") (pin "7") (pinfunction "A4_7") (pintype "bidirectional"))
      (node (ref "R12") (pin "1") (pinfunction "1_1") (pintype "passive"))
    )
    (net (code "58") (name "PBATT_SW") (class "Default")
      (node (ref "J4") (pin "3") (pinfunction "3_3") (pintype "bidirectional"))
      (node (ref "J8") (pin "5") (pinfunction "5_5") (pintype "bidirectional"))
      (node (ref "SJ1") (pin "1") (pinfunction "1_1") (pintype "passive"))
    )
    (net (code "59") (name "PGND") (class "Default")
      (node (ref "C3") (pin "2") (pinfunction "2_2") (pintype "passive"))
      (node (ref "C4") (pin "2") (pinfunction "2_2") (pintype "passive"))
      (node (ref "C5") (pin "K1") (pinfunction "K_K1") (pintype "passive"))
      (node (ref "H1") (pin "P$1") (pinfunction "MOUNT_P$1") (pintype "passive"))
      (node (ref "H2") (pin "P$1") (pinfunction "MOUNT_P$1") (pintype "passive"))
      (node (ref "H3") (pin "P$1") (pinfunction "MOUNT_P$1") (pintype "passive"))
      (node (ref "HBL") (pin "P$1") (pinfunction "MOUNT_P$1") (pintype "passive"))
      (node (ref "J5") (pin "1") (pinfunction "1_1") (pintype "bidirectional"))
      (node (ref "J5") (pin "4") (pinfunction "4_4") (pintype "bidirectional"))
      (node (ref "J6") (pin "1") (pinfunction "1_1") (pintype "bidirectional"))
      (node (ref "J6") (pin "4") (pinfunction "4_4") (pintype "bidirectional"))
      (node (ref "R1") (pin "2") (pinfunction "2_2") (pintype "passive"))
      (node (ref "R21") (pin "1") (pinfunction "1_1") (pintype "passive"))
      (node (ref "R22") (pin "1") (pinfunction "1_1") (pintype "passive"))
      (node (ref "R23") (pin "1") (pinfunction "1_1") (pintype "passive"))
      (node (ref "R24") (pin "1") (pinfunction "1_1") (pintype "passive"))
      (node (ref "R25") (pin "1") (pinfunction "1_1") (pintype "passive"))
      (node (ref "R26") (pin "1") (pinfunction "1_1") (pintype "passive"))
      (node (ref "R27") (pin "1") (pinfunction "1_1") (pintype "passive"))
      (node (ref "R28") (pin "1") (pinfunction "1_1") (pintype "passive"))
      (node (ref "SJ4") (pin "2") (pinfunction "2_2") (pintype "passive"))
      (node (ref "U2") (pin "A1") (pinfunction "PGND_A1") (pintype "bidirectional"))
      (node (ref "U2") (pin "A11") (pinfunction "PGND_A11") (pintype "bidirectional"))
      (node (ref "U2") (pin "A12") (pinfunction "PGND_A12") (pintype "bidirectional"))
      (node (ref "U2") (pin "A2") (pinfunction "PGND_A2") (pintype "bidirectional"))
      (node (ref "U2") (pin "A3") (pinfunction "PGND_A3") (pintype "bidirectional"))
      (node (ref "U2") (pin "A5") (pinfunction "SENSE-_A5") (pintype "bidirectional"))
      (node (ref "U2") (pin "A7") (pinfunction "SGND_A7") (pintype "bidirectional"))
      (node (ref "U2") (pin "B1") (pinfunction "PGND_B1") (pintype "bidirectional"))
      (node (ref "U2") (pin "B10") (pinfunction "PGND_B10") (pintype "bidirectional"))
      (node (ref "U2") (pin "B11") (pinfunction "PGND_B11") (pintype "bidirectional"))
      (node (ref "U2") (pin "B12") (pinfunction "PGND_B12") (pintype "bidirectional"))
      (node (ref "U2") (pin "B2") (pinfunction "PGND_B2") (pintype "bidirectional"))
      (node (ref "U2") (pin "B3") (pinfunction "PGND_B3") (pintype "bidirectional"))
      (node (ref "U2") (pin "B4") (pinfunction "PGND_B4") (pintype "bidirectional"))
      (node (ref "U2") (pin "C1") (pinfunction "PGND_C1") (pintype "bidirectional"))
      (node (ref "U2") (pin "C10") (pinfunction "PGND_C10") (pintype "bidirectional"))
      (node (ref "U2") (pin "C11") (pinfunction "PGND_C11") (pintype "bidirectional"))
      (node (ref "U2") (pin "C12") (pinfunction "PGND_C12") (pintype "bidirectional"))
      (node (ref "U2") (pin "C2") (pinfunction "PGND_C2") (pintype "bidirectional"))
      (node (ref "U2") (pin "C3") (pinfunction "PGND_C3") (pintype "bidirectional"))
      (node (ref "U2") (pin "C4") (pinfunction "PGND_C4") (pintype "bidirectional"))
      (node (ref "U2") (pin "C5") (pinfunction "PGND_C5") (pintype "bidirectional"))
      (node (ref "U2") (pin "C6") (pinfunction "PGND_C6") (pintype "bidirectional"))
      (node (ref "U2") (pin "C7") (pinfunction "PGND_C7") (pintype "bidirectional"))
      (node (ref "U2") (pin "C8") (pinfunction "PGND_C8") (pintype "bidirectional"))
      (node (ref "U2") (pin "C9") (pinfunction "PGND_C9") (pintype "bidirectional"))
      (node (ref "U2") (pin "D1") (pinfunction "PGND_D1") (pintype "bidirectional"))
      (node (ref "U2") (pin "D10") (pinfunction "PGND_D10") (pintype "bidirectional"))
      (node (ref "U2") (pin "D11") (pinfunction "PGND_D11") (pintype "bidirectional"))
      (node (ref "U2") (pin "D12") (pinfunction "PGND_D12") (pintype "bidirectional"))
      (node (ref "U2") (pin "D2") (pinfunction "PGND_D2") (pintype "bidirectional"))
      (node (ref "U2") (pin "D3") (pinfunction "PGND_D3") (pintype "bidirectional"))
      (node (ref "U2") (pin "D4") (pinfunction "PGND_D4") (pintype "bidirectional"))
      (node (ref "U2") (pin "D5") (pinfunction "PGND_D5") (pintype "bidirectional"))
      (node (ref "U2") (pin "D6") (pinfunction "PGND_D6") (pintype "bidirectional"))
      (node (ref "U2") (pin "D7") (pinfunction "PGND_D7") (pintype "bidirectional"))
      (node (ref "U2") (pin "D8") (pinfunction "PGND_D8") (pintype "bidirectional"))
      (node (ref "U2") (pin "D9") (pinfunction "PGND_D9") (pintype "bidirectional"))
      (node (ref "U2") (pin "E10") (pinfunction "PGND_E10") (pintype "bidirectional"))
      (node (ref "U2") (pin "E11") (pinfunction "PGND_E11") (pintype "bidirectional"))
      (node (ref "U2") (pin "E12") (pinfunction "PGND_E12") (pintype "bidirectional"))
      (node (ref "U2") (pin "E3") (pinfunction "PGND_E3") (pintype "bidirectional"))
      (node (ref "U2") (pin "E4") (pinfunction "PGND_E4") (pintype "bidirectional"))
      (node (ref "U2") (pin "E5") (pinfunction "PGND_E5") (pintype "bidirectional"))
      (node (ref "U2") (pin "E6") (pinfunction "PGND_E6") (pintype "bidirectional"))
      (node (ref "U2") (pin "E7") (pinfunction "PGND_E7") (pintype "bidirectional"))
      (node (ref "U2") (pin "E8") (pinfunction "PGND_E8") (pintype "bidirectional"))
      (node (ref "U2") (pin "E9") (pinfunction "PGND_E9") (pintype "bidirectional"))
      (node (ref "U3") (pin "1") (pinfunction "GND_1") (pintype "bidirectional"))
      (node (ref "U3") (pin "10") (pinfunction "GND_10") (pintype "bidirectional"))
      (node (ref "U4") (pin "1") (pinfunction "GND_1") (pintype "bidirectional"))
      (node (ref "U4") (pin "10") (pinfunction "GND_10") (pintype "bidirectional"))
    )
    (net (code "60") (name "PGOOD_PMA") (class "Default")
      (node (ref "U2") (pin "B5") (pinfunction "PGOOD_B5") (pintype "bidirectional"))
    )
    (net (code "61") (name "RSENSE") (class "Default")
      (node (ref "R1") (pin "1") (pinfunction "1_1") (pintype "passive"))
      (node (ref "U2") (pin "A4") (pinfunction "SENSE+_A4") (pintype "bidirectional"))
      (node (ref "U2") (pin "F10") (pinfunction "R_SENSE_F10") (pintype "bidirectional"))
      (node (ref "U2") (pin "F11") (pinfunction "R_SENSE_F11") (pintype "bidirectional"))
      (node (ref "U2") (pin "F12") (pinfunction "R_SENSE_F12") (pintype "bidirectional"))
      (node (ref "U2") (pin "G10") (pinfunction "R_SENSE_G10") (pintype "bidirectional"))
      (node (ref "U2") (pin "G11") (pinfunction "R_SENSE_G11") (pintype "bidirectional"))
      (node (ref "U2") (pin "G12") (pinfunction "R_SENSE_G12") (pintype "bidirectional"))
      (node (ref "U2") (pin "G5") (pinfunction "R_SENSE_G5") (pintype "bidirectional"))
      (node (ref "U2") (pin "G6") (pinfunction "R_SENSE_G6") (pintype "bidirectional"))
      (node (ref "U2") (pin "G7") (pinfunction "R_SENSE_G7") (pintype "bidirectional"))
      (node (ref "U2") (pin "G8") (pinfunction "R_SENSE_G8") (pintype "bidirectional"))
      (node (ref "U2") (pin "G9") (pinfunction "R_SENSE_G9") (pintype "bidirectional"))
      (node (ref "U2") (pin "H10") (pinfunction "R_SENSE_H10") (pintype "bidirectional"))
      (node (ref "U2") (pin "H11") (pinfunction "R_SENSE_H11") (pintype "bidirectional"))
      (node (ref "U2") (pin "H12") (pinfunction "R_SENSE_H12") (pintype "bidirectional"))
      (node (ref "U2") (pin "H5") (pinfunction "R_SENSE_H5") (pintype "bidirectional"))
      (node (ref "U2") (pin "H6") (pinfunction "R_SENSE_H6") (pintype "bidirectional"))
      (node (ref "U2") (pin "H7") (pinfunction "R_SENSE_H7") (pintype "bidirectional"))
      (node (ref "U2") (pin "H8") (pinfunction "R_SENSE_H8") (pintype "bidirectional"))
      (node (ref "U2") (pin "H9") (pinfunction "R_SENSE_H9") (pintype "bidirectional"))
      (node (ref "U2") (pin "J5") (pinfunction "R_SENSE_J5") (pintype "bidirectional"))
      (node (ref "U2") (pin "J6") (pinfunction "R_SENSE_J6") (pintype "bidirectional"))
      (node (ref "U2") (pin "J7") (pinfunction "R_SENSE_J7") (pintype "bidirectional"))
      (node (ref "U2") (pin "K5") (pinfunction "R_SENSE_K5") (pintype "bidirectional"))
      (node (ref "U2") (pin "K6") (pinfunction "R_SENSE_K6") (pintype "bidirectional"))
      (node (ref "U2") (pin "L5") (pinfunction "R_SENSE_L5") (pintype "bidirectional"))
      (node (ref "U2") (pin "L6") (pinfunction "R_SENSE_L6") (pintype "bidirectional"))
      (node (ref "U2") (pin "M5") (pinfunction "R_SENSE_M5") (pintype "bidirectional"))
      (node (ref "U2") (pin "M6") (pinfunction "R_SENSE_M6") (pintype "bidirectional"))
    )
    (net (code "62") (name "RUN_PMA") (class "Default")
      (node (ref "U2") (pin "A8") (pinfunction "RUN_A8") (pintype "bidirectional"))
    )
    (net (code "63") (name "SGND") (class "Default")
      (node (ref "J4") (pin "6") (pinfunction "6_6") (pintype "bidirectional"))
      (node (ref "J5") (pin "12") (pinfunction "12_12") (pintype "bidirectional"))
      (node (ref "J5") (pin "9") (pinfunction "9_9") (pintype "bidirectional"))
      (node (ref "J6") (pin "12") (pinfunction "12_12") (pintype "bidirectional"))
      (node (ref "J6") (pin "9") (pinfunction "9_9") (pintype "bidirectional"))
      (node (ref "OK1") (pin "2") (pinfunction "K1_2") (pintype "bidirectional"))
      (node (ref "OK1") (pin "4") (pinfunction "K2_4") (pintype "bidirectional"))
      (node (ref "OK1") (pin "6") (pinfunction "K3_6") (pintype "bidirectional"))
      (node (ref "OK1") (pin "8") (pinfunction "K4_8") (pintype "bidirectional"))
      (node (ref "OK2") (pin "2") (pinfunction "K1_2") (pintype "bidirectional"))
      (node (ref "OK2") (pin "4") (pinfunction "K2_4") (pintype "bidirectional"))
      (node (ref "OK2") (pin "6") (pinfunction "K3_6") (pintype "bidirectional"))
      (node (ref "OK2") (pin "8") (pinfunction "K4_8") (pintype "bidirectional"))
      (node (ref "OK3") (pin "15") (pinfunction "E1_15") (pintype "bidirectional"))
      (node (ref "R4") (pin "2") (pinfunction "2_2") (pintype "passive"))
      (node (ref "SJ3") (pin "2") (pinfunction "2_2") (pintype "passive"))
    )
    (net (code "64") (name "SW_P18H1") (class "Default")
      (node (ref "R9") (pin "2") (pinfunction "2_2") (pintype "passive"))
      (node (ref "U1") (pin "35") (pinfunction "SDHC_DAT0_35") (pintype "bidirectional"))
    )
    (net (code "65") (name "SW_P18H2") (class "Default")
      (node (ref "R10") (pin "2") (pinfunction "2_2") (pintype "passive"))
      (node (ref "U1") (pin "34") (pinfunction "UART1_TX_34") (pintype "bidirectional"))
    )
    (net (code "66") (name "SW_P18H3") (class "Default")
      (node (ref "R11") (pin "2") (pinfunction "2_2") (pintype "passive"))
      (node (ref "U1") (pin "33") (pinfunction "SDHC_CMD_33") (pintype "bidirectional"))
    )
    (net (code "67") (name "SW_P18H4") (class "Default")
      (node (ref "R12") (pin "2") (pinfunction "2_2") (pintype "passive"))
      (node (ref "U1") (pin "32") (pinfunction "UART1_RX_32") (pintype "bidirectional"))
    )
    (net (code "68") (name "SW_P18L1") (class "Default")
      (node (ref "R5") (pin "2") (pinfunction "2_2") (pintype "passive"))
      (node (ref "U1") (pin "39") (pinfunction "SDHC_DAT2_39") (pintype "bidirectional"))
    )
    (net (code "69") (name "SW_P18L2") (class "Default")
      (node (ref "R6") (pin "2") (pinfunction "2_2") (pintype "passive"))
      (node (ref "U1") (pin "38") (pinfunction "UART1_CTS_38") (pintype "bidirectional"))
    )
    (net (code "70") (name "SW_P18L3") (class "Default")
      (node (ref "R7") (pin "2") (pinfunction "2_2") (pintype "passive"))
      (node (ref "U1") (pin "37") (pinfunction "SDHC_DAT1_37") (pintype "bidirectional"))
    )
    (net (code "71") (name "SW_P18L4") (class "Default")
      (node (ref "R8") (pin "2") (pinfunction "2_2") (pintype "passive"))
      (node (ref "U1") (pin "36") (pinfunction "UART1_RTS_36") (pintype "bidirectional"))
    )
    (net (code "72") (name "SW_RUNPMA") (class "Default")
      (node (ref "U1") (pin "23") (pinfunction "T2IN_23") (pintype "bidirectional"))
    )
    (net (code "73") (name "SW_TP1") (class "Default")
      (node (ref "J4") (pin "7") (pinfunction "7_7") (pintype "bidirectional"))
      (node (ref "OK3") (pin "2") (pinfunction "K1_2") (pintype "bidirectional"))
      (node (ref "U1") (pin "31") (pinfunction "SDHC_CLK_31") (pintype "bidirectional"))
    )
    (net (code "74") (name "TP1_OUT") (class "Default")
      (node (ref "J4") (pin "8") (pinfunction "8_8") (pintype "bidirectional"))
      (node (ref "J5") (pin "3") (pinfunction "3_3") (pintype "bidirectional"))
      (node (ref "J5") (pin "6") (pinfunction "6_6") (pintype "bidirectional"))
      (node (ref "J6") (pin "3") (pinfunction "3_3") (pintype "bidirectional"))
      (node (ref "J6") (pin "6") (pinfunction "6_6") (pintype "bidirectional"))
      (node (ref "OK3") (pin "16") (pinfunction "C1_16") (pintype "bidirectional"))
      (node (ref "R34") (pin "1") (pinfunction "1_1") (pintype "passive"))
    )
    (net (code "75") (name "VBATT_IN") (class "Default")
      (node (ref "C1") (pin "A1") (pinfunction "A_A1") (pintype "passive"))
      (node (ref "L2") (pin "1") (pinfunction "1_1") (pintype "bidirectional"))
      (node (ref "SJ1") (pin "2") (pinfunction "2_2") (pintype "passive"))
    )
    (net (code "76") (name "VIN") (class "Default")
      (node (ref "C2") (pin "1") (pinfunction "1_1") (pintype "passive"))
      (node (ref "L2") (pin "2") (pinfunction "2_2") (pintype "bidirectional"))
      (node (ref "U2") (pin "J10") (pinfunction "V_IN_J10") (pintype "bidirectional"))
      (node (ref "U2") (pin "J11") (pinfunction "V_IN_J11") (pintype "bidirectional"))
      (node (ref "U2") (pin "J12") (pinfunction "V_IN_J12") (pintype "bidirectional"))
      (node (ref "U2") (pin "K10") (pinfunction "V_IN_K10") (pintype "bidirectional"))
      (node (ref "U2") (pin "K11") (pinfunction "V_IN_K11") (pintype "bidirectional"))
      (node (ref "U2") (pin "K12") (pinfunction "V_IN_K12") (pintype "bidirectional"))
      (node (ref "U2") (pin "L10") (pinfunction "V_IN_L10") (pintype "bidirectional"))
      (node (ref "U2") (pin "L11") (pinfunction "V_IN_L11") (pintype "bidirectional"))
      (node (ref "U2") (pin "L12") (pinfunction "V_IN_L12") (pintype "bidirectional"))
      (node (ref "U2") (pin "M10") (pinfunction "V_IN_M10") (pintype "bidirectional"))
      (node (ref "U2") (pin "M11") (pinfunction "V_IN_M11") (pintype "bidirectional"))
      (node (ref "U2") (pin "M12") (pinfunction "V_IN_M12") (pintype "bidirectional"))
    )
    (net (code "77") (name "VOUT") (class "Default")
      (node (ref "C3") (pin "1") (pinfunction "1_1") (pintype "passive"))
      (node (ref "C4") (pin "1") (pinfunction "1_1") (pintype "passive"))
      (node (ref "L3") (pin "1") (pinfunction "1_1") (pintype "bidirectional"))
      (node (ref "U2") (pin "E1") (pinfunction "V_OUT_E1") (pintype "bidirectional"))
      (node (ref "U2") (pin "E2") (pinfunction "V_OUT_E2") (pintype "bidirectional"))
      (node (ref "U2") (pin "F1") (pinfunction "V_OUT_F1") (pintype "bidirectional"))
      (node (ref "U2") (pin "F2") (pinfunction "V_OUT_F2") (pintype "bidirectional"))
      (node (ref "U2") (pin "F3") (pinfunction "V_OUT_F3") (pintype "bidirectional"))
      (node (ref "U2") (pin "F4") (pinfunction "V_OUT_F4") (pintype "bidirectional"))
      (node (ref "U2") (pin "G1") (pinfunction "V_OUT_G1") (pintype "bidirectional"))
      (node (ref "U2") (pin "G2") (pinfunction "V_OUT_G2") (pintype "bidirectional"))
      (node (ref "U2") (pin "G3") (pinfunction "V_OUT_G3") (pintype "bidirectional"))
      (node (ref "U2") (pin "G4") (pinfunction "V_OUT_G4") (pintype "bidirectional"))
      (node (ref "U2") (pin "H2") (pinfunction "V_OUT_H2") (pintype "bidirectional"))
      (node (ref "U2") (pin "H3") (pinfunction "V_OUT_H3") (pintype "bidirectional"))
      (node (ref "U2") (pin "H4") (pinfunction "V_OUT_H4") (pintype "bidirectional"))
      (node (ref "U2") (pin "VOUT") (pinfunction "V_OUT_VOUT") (pintype "bidirectional"))
    )
    (net (code "78") (name "VOUTA") (class "Default")
      (node (ref "C5") (pin "A1") (pinfunction "A_A1") (pintype "passive"))
      (node (ref "L3") (pin "2") (pinfunction "2_2") (pintype "bidirectional"))
      (node (ref "Q11") (pin "D") (pinfunction "D_D") (pintype "bidirectional"))
      (node (ref "Q13") (pin "D") (pinfunction "D_D") (pintype "bidirectional"))
      (node (ref "Q15") (pin "D") (pinfunction "D_D") (pintype "bidirectional"))
      (node (ref "Q9") (pin "D") (pinfunction "D_D") (pintype "bidirectional"))
      (node (ref "R13") (pin "1") (pinfunction "1_1") (pintype "passive"))
      (node (ref "R14") (pin "1") (pinfunction "1_1") (pintype "passive"))
      (node (ref "R15") (pin "1") (pinfunction "1_1") (pintype "passive"))
      (node (ref "R16") (pin "1") (pinfunction "1_1") (pintype "passive"))
      (node (ref "R17") (pin "1") (pinfunction "1_1") (pintype "passive"))
      (node (ref "R18") (pin "1") (pinfunction "1_1") (pintype "passive"))
      (node (ref "R19") (pin "1") (pinfunction "1_1") (pintype "passive"))
      (node (ref "R20") (pin "1") (pinfunction "1_1") (pintype "passive"))
      (node (ref "R29") (pin "2") (pinfunction "2_2") (pintype "passive"))
      (node (ref "R30") (pin "2") (pinfunction "2_2") (pintype "passive"))
      (node (ref "R31") (pin "2") (pinfunction "2_2") (pintype "passive"))
      (node (ref "R32") (pin "2") (pinfunction "2_2") (pintype "passive"))
      (node (ref "U3") (pin "11") (pinfunction "V+_11") (pintype "bidirectional"))
      (node (ref "U3") (pin "13") (pinfunction "SENSE4_13") (pintype "bidirectional"))
      (node (ref "U3") (pin "15") (pinfunction "SENSE3_15") (pintype "bidirectional"))
      (node (ref "U3") (pin "17") (pinfunction "SENSE2_17") (pintype "bidirectional"))
      (node (ref "U3") (pin "19") (pinfunction "SENSE1_19") (pintype "bidirectional"))
      (node (ref "U3") (pin "20") (pinfunction "V+_20") (pintype "bidirectional"))
      (node (ref "U4") (pin "11") (pinfunction "V+_11") (pintype "bidirectional"))
      (node (ref "U4") (pin "13") (pinfunction "SENSE4_13") (pintype "bidirectional"))
      (node (ref "U4") (pin "15") (pinfunction "SENSE3_15") (pintype "bidirectional"))
      (node (ref "U4") (pin "17") (pinfunction "SENSE2_17") (pintype "bidirectional"))
      (node (ref "U4") (pin "19") (pinfunction "SENSE1_19") (pintype "bidirectional"))
      (node (ref "U4") (pin "20") (pinfunction "V+_20") (pintype "bidirectional"))
    )
    (net (code "79") (name "unconnected-(J2-+5V_SW-Pad33)") (class "Default")
      (node (ref "J2") (pin "33") (pinfunction "+5V_SW_33") (pintype "bidirectional"))
    )
    (net (code "80") (name "unconnected-(J2-+5V_SYS-Pad77)") (class "Default")
      (node (ref "J2") (pin "77") (pinfunction "+5V_SYS_77") (pintype "bidirectional"))
    )
    (net (code "81") (name "unconnected-(J2-+5V_SYS-Pad78)") (class "Default")
      (node (ref "J2") (pin "78") (pinfunction "+5V_SYS_78") (pintype "bidirectional"))
    )
    (net (code "82") (name "unconnected-(J2-+5V_USB-Pad32)") (class "Default")
      (node (ref "J2") (pin "32") (pinfunction "+5V_USB_32") (pintype "bidirectional"))
    )
    (net (code "83") (name "unconnected-(J2--CTS_MHX-Pad35)") (class "Default")
      (node (ref "J2") (pin "35") (pinfunction "-CTS_MHX_35") (pintype "bidirectional"))
    )
    (net (code "84") (name "unconnected-(J2--DSR_MHX-Pad37)") (class "Default")
      (node (ref "J2") (pin "37") (pinfunction "-DSR_MHX_37") (pintype "bidirectional"))
    )
    (net (code "85") (name "unconnected-(J2--DTR_MHX-Pad38)") (class "Default")
      (node (ref "J2") (pin "38") (pinfunction "-DTR_MHX_38") (pintype "bidirectional"))
    )
    (net (code "86") (name "unconnected-(J2--FAULT-Pad25)") (class "Default")
      (node (ref "J2") (pin "25") (pinfunction "-FAULT_25") (pintype "bidirectional"))
    )
    (net (code "87") (name "unconnected-(J2--RESET-Pad29)") (class "Default")
      (node (ref "J2") (pin "29") (pinfunction "-RESET_29") (pintype "bidirectional"))
    )
    (net (code "88") (name "unconnected-(J2--RST_MHX-Pad34)") (class "Default")
      (node (ref "J2") (pin "34") (pinfunction "-RST_MHX_34") (pintype "bidirectional"))
    )
    (net (code "89") (name "unconnected-(J2--RTS_MHX-Pad36)") (class "Default")
      (node (ref "J2") (pin "36") (pinfunction "-RTS_MHX_36") (pintype "bidirectional"))
    )
    (net (code "90") (name "unconnected-(J2-OFF_VCC-Pad31)") (class "Default")
      (node (ref "J2") (pin "31") (pinfunction "OFF_VCC_31") (pintype "bidirectional"))
    )
    (net (code "91") (name "unconnected-(J2-P1.0-Pad68)") (class "Default")
      (node (ref "J2") (pin "68") (pinfunction "P1.0_68") (pintype "bidirectional"))
    )
    (net (code "92") (name "unconnected-(J2-P1.1-Pad67)") (class "Default")
      (node (ref "J2") (pin "67") (pinfunction "P1.1_67") (pintype "bidirectional"))
    )
    (net (code "93") (name "unconnected-(J2-P1.2-Pad66)") (class "Default")
      (node (ref "J2") (pin "66") (pinfunction "P1.2_66") (pintype "bidirectional"))
    )
    (net (code "94") (name "unconnected-(J2-P1.3-Pad65)") (class "Default")
      (node (ref "J2") (pin "65") (pinfunction "P1.3_65") (pintype "bidirectional"))
    )
    (net (code "95") (name "unconnected-(J2-P1.4-Pad64)") (class "Default")
      (node (ref "J2") (pin "64") (pinfunction "P1.4_64") (pintype "bidirectional"))
    )
    (net (code "96") (name "unconnected-(J2-P1.5-Pad63)") (class "Default")
      (node (ref "J2") (pin "63") (pinfunction "P1.5_63") (pintype "bidirectional"))
    )
    (net (code "97") (name "unconnected-(J2-P1.6-Pad62)") (class "Default")
      (node (ref "J2") (pin "62") (pinfunction "P1.6_62") (pintype "bidirectional"))
    )
    (net (code "98") (name "unconnected-(J2-P1.7-Pad61)") (class "Default")
      (node (ref "J2") (pin "61") (pinfunction "P1.7_61") (pintype "bidirectional"))
    )
    (net (code "99") (name "unconnected-(J2-P2.0-Pad76)") (class "Default")
      (node (ref "J2") (pin "76") (pinfunction "P2.0_76") (pintype "bidirectional"))
    )
    (net (code "100") (name "unconnected-(J2-P2.1-Pad75)") (class "Default")
      (node (ref "J2") (pin "75") (pinfunction "P2.1_75") (pintype "bidirectional"))
    )
    (net (code "101") (name "unconnected-(J2-P2.2-Pad74)") (class "Default")
      (node (ref "J2") (pin "74") (pinfunction "P2.2_74") (pintype "bidirectional"))
    )
    (net (code "102") (name "unconnected-(J2-P2.3-Pad73)") (class "Default")
      (node (ref "J2") (pin "73") (pinfunction "P2.3_73") (pintype "bidirectional"))
    )
    (net (code "103") (name "unconnected-(J2-P2.4-Pad72)") (class "Default")
      (node (ref "J2") (pin "72") (pinfunction "P2.4_72") (pintype "bidirectional"))
    )
    (net (code "104") (name "unconnected-(J2-P2.5-Pad71)") (class "Default")
      (node (ref "J2") (pin "71") (pinfunction "P2.5_71") (pintype "bidirectional"))
    )
    (net (code "105") (name "unconnected-(J2-P2.6-Pad70)") (class "Default")
      (node (ref "J2") (pin "70") (pinfunction "P2.6_70") (pintype "bidirectional"))
    )
    (net (code "106") (name "unconnected-(J2-P2.7-Pad69)") (class "Default")
      (node (ref "J2") (pin "69") (pinfunction "P2.7_69") (pintype "bidirectional"))
    )
    (net (code "107") (name "unconnected-(J2-P3.0-Pad24)") (class "Default")
      (node (ref "J2") (pin "24") (pinfunction "P3.0_24") (pintype "bidirectional"))
    )
    (net (code "108") (name "unconnected-(J2-P3.1-Pad23)") (class "Default")
      (node (ref "J2") (pin "23") (pinfunction "P3.1_23") (pintype "bidirectional"))
    )
    (net (code "109") (name "unconnected-(J2-P3.2-Pad22)") (class "Default")
      (node (ref "J2") (pin "22") (pinfunction "P3.2_22") (pintype "bidirectional"))
    )
    (net (code "110") (name "unconnected-(J2-P3.3-Pad21)") (class "Default")
      (node (ref "J2") (pin "21") (pinfunction "P3.3_21") (pintype "bidirectional"))
    )
    (net (code "111") (name "unconnected-(J2-P3.4-Pad20)") (class "Default")
      (node (ref "J2") (pin "20") (pinfunction "P3.4_20") (pintype "bidirectional"))
    )
    (net (code "112") (name "unconnected-(J2-P3.5-Pad19)") (class "Default")
      (node (ref "J2") (pin "19") (pinfunction "P3.5_19") (pintype "bidirectional"))
    )
    (net (code "113") (name "unconnected-(J2-P3.6-Pad18)") (class "Default")
      (node (ref "J2") (pin "18") (pinfunction "P3.6_18") (pintype "bidirectional"))
    )
    (net (code "114") (name "unconnected-(J2-P3.7-Pad17)") (class "Default")
      (node (ref "J2") (pin "17") (pinfunction "P3.7_17") (pintype "bidirectional"))
    )
    (net (code "115") (name "unconnected-(J2-P4.0-Pad16)") (class "Default")
      (node (ref "J2") (pin "16") (pinfunction "P4.0_16") (pintype "bidirectional"))
    )
    (net (code "116") (name "unconnected-(J2-P4.1-Pad15)") (class "Default")
      (node (ref "J2") (pin "15") (pinfunction "P4.1_15") (pintype "bidirectional"))
    )
    (net (code "117") (name "unconnected-(J2-P4.2-Pad14)") (class "Default")
      (node (ref "J2") (pin "14") (pinfunction "P4.2_14") (pintype "bidirectional"))
    )
    (net (code "118") (name "unconnected-(J2-P4.3-Pad13)") (class "Default")
      (node (ref "J2") (pin "13") (pinfunction "P4.3_13") (pintype "bidirectional"))
    )
    (net (code "119") (name "unconnected-(J2-P4.4-Pad12)") (class "Default")
      (node (ref "J2") (pin "12") (pinfunction "P4.4_12") (pintype "bidirectional"))
    )
    (net (code "120") (name "unconnected-(J2-P4.5-Pad11)") (class "Default")
      (node (ref "J2") (pin "11") (pinfunction "P4.5_11") (pintype "bidirectional"))
    )
    (net (code "121") (name "unconnected-(J2-P4.6-Pad10)") (class "Default")
      (node (ref "J2") (pin "10") (pinfunction "P4.6_10") (pintype "bidirectional"))
    )
    (net (code "122") (name "unconnected-(J2-P4.7-Pad9)") (class "Default")
      (node (ref "J2") (pin "9") (pinfunction "P4.7_9") (pintype "bidirectional"))
    )
    (net (code "123") (name "unconnected-(J2-P5.0-Pad8)") (class "Default")
      (node (ref "J2") (pin "8") (pinfunction "P5.0_8") (pintype "bidirectional"))
    )
    (net (code "124") (name "unconnected-(J2-P5.1-Pad7)") (class "Default")
      (node (ref "J2") (pin "7") (pinfunction "P5.1_7") (pintype "bidirectional"))
    )
    (net (code "125") (name "unconnected-(J2-P5.2-Pad6)") (class "Default")
      (node (ref "J2") (pin "6") (pinfunction "P5.2_6") (pintype "bidirectional"))
    )
    (net (code "126") (name "unconnected-(J2-P5.3-Pad5)") (class "Default")
      (node (ref "J2") (pin "5") (pinfunction "P5.3_5") (pintype "bidirectional"))
    )
    (net (code "127") (name "unconnected-(J2-P5.4-Pad4)") (class "Default")
      (node (ref "J2") (pin "4") (pinfunction "P5.4_4") (pintype "bidirectional"))
    )
    (net (code "128") (name "unconnected-(J2-P5.5-Pad3)") (class "Default")
      (node (ref "J2") (pin "3") (pinfunction "P5.5_3") (pintype "bidirectional"))
    )
    (net (code "129") (name "unconnected-(J2-P5.6-Pad2)") (class "Default")
      (node (ref "J2") (pin "2") (pinfunction "P5.6_2") (pintype "bidirectional"))
    )
    (net (code "130") (name "unconnected-(J2-P5.7-Pad1)") (class "Default")
      (node (ref "J2") (pin "1") (pinfunction "P5.7_1") (pintype "bidirectional"))
    )
    (net (code "131") (name "unconnected-(J2-P6.0-Pad60)") (class "Default")
      (node (ref "J2") (pin "60") (pinfunction "P6.0_60") (pintype "bidirectional"))
    )
    (net (code "132") (name "unconnected-(J2-P6.1-Pad59)") (class "Default")
      (node (ref "J2") (pin "59") (pinfunction "P6.1_59") (pintype "bidirectional"))
    )
    (net (code "133") (name "unconnected-(J2-P6.2-Pad58)") (class "Default")
      (node (ref "J2") (pin "58") (pinfunction "P6.2_58") (pintype "bidirectional"))
    )
    (net (code "134") (name "unconnected-(J2-P6.3-Pad57)") (class "Default")
      (node (ref "J2") (pin "57") (pinfunction "P6.3_57") (pintype "bidirectional"))
    )
    (net (code "135") (name "unconnected-(J2-P6.4-Pad56)") (class "Default")
      (node (ref "J2") (pin "56") (pinfunction "P6.4_56") (pintype "bidirectional"))
    )
    (net (code "136") (name "unconnected-(J2-P6.5-Pad55)") (class "Default")
      (node (ref "J2") (pin "55") (pinfunction "P6.5_55") (pintype "bidirectional"))
    )
    (net (code "137") (name "unconnected-(J2-P6.6-Pad54)") (class "Default")
      (node (ref "J2") (pin "54") (pinfunction "P6.6_54") (pintype "bidirectional"))
    )
    (net (code "138") (name "unconnected-(J2-P6.7-Pad53)") (class "Default")
      (node (ref "J2") (pin "53") (pinfunction "P6.7_53") (pintype "bidirectional"))
    )
    (net (code "139") (name "unconnected-(J2-RSVD0-Pad44)") (class "Default")
      (node (ref "J2") (pin "44") (pinfunction "RSVD0_44") (pintype "bidirectional"))
    )
    (net (code "140") (name "unconnected-(J2-RSVD1-Pad45)") (class "Default")
      (node (ref "J2") (pin "45") (pinfunction "RSVD1_45") (pintype "bidirectional"))
    )
    (net (code "141") (name "unconnected-(J2-RSVD2-Pad46)") (class "Default")
      (node (ref "J2") (pin "46") (pinfunction "RSVD2_46") (pintype "bidirectional"))
    )
    (net (code "142") (name "unconnected-(J2-RXD_MHX-Pad40)") (class "Default")
      (node (ref "J2") (pin "40") (pinfunction "RXD_MHX_40") (pintype "bidirectional"))
    )
    (net (code "143") (name "unconnected-(J2-SENSE-Pad27)") (class "Default")
      (node (ref "J2") (pin "27") (pinfunction "SENSE_27") (pintype "bidirectional"))
    )
    (net (code "144") (name "unconnected-(J2-SW0-Pad85)") (class "Default")
      (node (ref "J2") (pin "85") (pinfunction "SW0_85") (pintype "bidirectional"))
    )
    (net (code "145") (name "unconnected-(J2-SW0-Pad86)") (class "Default")
      (node (ref "J2") (pin "86") (pinfunction "SW0_86") (pintype "bidirectional"))
    )
    (net (code "146") (name "unconnected-(J2-SW1-Pad87)") (class "Default")
      (node (ref "J2") (pin "87") (pinfunction "SW1_87") (pintype "bidirectional"))
    )
    (net (code "147") (name "unconnected-(J2-SW1-Pad88)") (class "Default")
      (node (ref "J2") (pin "88") (pinfunction "SW1_88") (pintype "bidirectional"))
    )
    (net (code "148") (name "unconnected-(J2-SW2-Pad89)") (class "Default")
      (node (ref "J2") (pin "89") (pinfunction "SW2_89") (pintype "bidirectional"))
    )
    (net (code "149") (name "unconnected-(J2-SW2-Pad90)") (class "Default")
      (node (ref "J2") (pin "90") (pinfunction "SW2_90") (pintype "bidirectional"))
    )
    (net (code "150") (name "unconnected-(J2-SW3-Pad91)") (class "Default")
      (node (ref "J2") (pin "91") (pinfunction "SW3_91") (pintype "bidirectional"))
    )
    (net (code "151") (name "unconnected-(J2-SW3-Pad92)") (class "Default")
      (node (ref "J2") (pin "92") (pinfunction "SW3_92") (pintype "bidirectional"))
    )
    (net (code "152") (name "unconnected-(J2-SW4-Pad93)") (class "Default")
      (node (ref "J2") (pin "93") (pinfunction "SW4_93") (pintype "bidirectional"))
    )
    (net (code "153") (name "unconnected-(J2-SW4-Pad94)") (class "Default")
      (node (ref "J2") (pin "94") (pinfunction "SW4_94") (pintype "bidirectional"))
    )
    (net (code "154") (name "unconnected-(J2-SW5-Pad95)") (class "Default")
      (node (ref "J2") (pin "95") (pinfunction "SW5_95") (pintype "bidirectional"))
    )
    (net (code "155") (name "unconnected-(J2-SW5-Pad96)") (class "Default")
      (node (ref "J2") (pin "96") (pinfunction "SW5_96") (pintype "bidirectional"))
    )
    (net (code "156") (name "unconnected-(J2-TXD_MHX-Pad39)") (class "Default")
      (node (ref "J2") (pin "39") (pinfunction "TXD_MHX_39") (pintype "bidirectional"))
    )
    (net (code "157") (name "unconnected-(J2-USER0-Pad47)") (class "Default")
      (node (ref "J2") (pin "47") (pinfunction "USER0_47") (pintype "bidirectional"))
    )
    (net (code "158") (name "unconnected-(J2-USER1-Pad48)") (class "Default")
      (node (ref "J2") (pin "48") (pinfunction "USER1_48") (pintype "bidirectional"))
    )
    (net (code "159") (name "unconnected-(J2-USER2-Pad49)") (class "Default")
      (node (ref "J2") (pin "49") (pinfunction "USER2_49") (pintype "bidirectional"))
    )
    (net (code "160") (name "unconnected-(J2-USER3-Pad50)") (class "Default")
      (node (ref "J2") (pin "50") (pinfunction "USER3_50") (pintype "bidirectional"))
    )
    (net (code "161") (name "unconnected-(J2-USER4-Pad51)") (class "Default")
      (node (ref "J2") (pin "51") (pinfunction "USER4_51") (pintype "bidirectional"))
    )
    (net (code "162") (name "unconnected-(J2-USER5-Pad52)") (class "Default")
      (node (ref "J2") (pin "52") (pinfunction "USER5_52") (pintype "bidirectional"))
    )
    (net (code "163") (name "unconnected-(J2-USER6-Pad99)") (class "Default")
      (node (ref "J2") (pin "99") (pinfunction "USER6_99") (pintype "bidirectional"))
    )
    (net (code "164") (name "unconnected-(J2-USER7-Pad100)") (class "Default")
      (node (ref "J2") (pin "100") (pinfunction "USER7_100") (pintype "bidirectional"))
    )
    (net (code "165") (name "unconnected-(J2-USER8-Pad101)") (class "Default")
      (node (ref "J2") (pin "101") (pinfunction "USER8_101") (pintype "bidirectional"))
    )
    (net (code "166") (name "unconnected-(J2-USER9-Pad102)") (class "Default")
      (node (ref "J2") (pin "102") (pinfunction "USER9_102") (pintype "bidirectional"))
    )
    (net (code "167") (name "unconnected-(J2-USER10-Pad103)") (class "Default")
      (node (ref "J2") (pin "103") (pinfunction "USER10_103") (pintype "bidirectional"))
    )
    (net (code "168") (name "unconnected-(J2-USER11-Pad104)") (class "Default")
      (node (ref "J2") (pin "104") (pinfunction "USER11_104") (pintype "bidirectional"))
    )
    (net (code "169") (name "unconnected-(J2-VBACKUP-Pad42)") (class "Default")
      (node (ref "J2") (pin "42") (pinfunction "VBACKUP_42") (pintype "bidirectional"))
    )
    (net (code "170") (name "unconnected-(J2-VBATT-Pad97)") (class "Default")
      (node (ref "J2") (pin "97") (pinfunction "VBATT_97") (pintype "bidirectional"))
    )
    (net (code "171") (name "unconnected-(J2-VBATT-Pad98)") (class "Default")
      (node (ref "J2") (pin "98") (pinfunction "VBATT_98") (pintype "bidirectional"))
    )
    (net (code "172") (name "unconnected-(J2-VCC_SYS-Pad79)") (class "Default")
      (node (ref "J2") (pin "79") (pinfunction "VCC_SYS_79") (pintype "bidirectional"))
    )
    (net (code "173") (name "unconnected-(J2-VCC_SYS-Pad80)") (class "Default")
      (node (ref "J2") (pin "80") (pinfunction "VCC_SYS_80") (pintype "bidirectional"))
    )
    (net (code "174") (name "unconnected-(J2-VEREF+-Pad28)") (class "Default")
      (node (ref "J2") (pin "28") (pinfunction "VEREF+_28") (pintype "bidirectional"))
    )
    (net (code "175") (name "unconnected-(J2-VREF+-Pad26)") (class "Default")
      (node (ref "J2") (pin "26") (pinfunction "VREF+_26") (pintype "bidirectional"))
    )
    (net (code "176") (name "unconnected-(J2-VREF--Pad30)") (class "Default")
      (node (ref "J2") (pin "30") (pinfunction "VREF-_30") (pintype "bidirectional"))
    )
    (net (code "177") (name "unconnected-(J4-Pad9)") (class "Default")
      (node (ref "J4") (pin "9") (pinfunction "9_9") (pintype "bidirectional"))
    )
    (net (code "178") (name "unconnected-(J4-Pad10)") (class "Default")
      (node (ref "J4") (pin "10") (pinfunction "10_10") (pintype "bidirectional"))
    )
    (net (code "179") (name "unconnected-(J5-Pad2)") (class "Default")
      (node (ref "J5") (pin "2") (pinfunction "2_2") (pintype "bidirectional"))
    )
    (net (code "180") (name "unconnected-(J5-Pad5)") (class "Default")
      (node (ref "J5") (pin "5") (pinfunction "5_5") (pintype "bidirectional"))
    )
    (net (code "181") (name "unconnected-(J6-Pad2)") (class "Default")
      (node (ref "J6") (pin "2") (pinfunction "2_2") (pintype "bidirectional"))
    )
    (net (code "182") (name "unconnected-(J6-Pad5)") (class "Default")
      (node (ref "J6") (pin "5") (pinfunction "5_5") (pintype "bidirectional"))
    )
    (net (code "183") (name "unconnected-(J8-Pad3)") (class "Default")
      (node (ref "J8") (pin "3") (pinfunction "3_3") (pintype "bidirectional"))
    )
    (net (code "184") (name "unconnected-(J8-Pad6)") (class "Default")
      (node (ref "J8") (pin "6") (pinfunction "6_6") (pintype "bidirectional"))
    )
    (net (code "185") (name "unconnected-(OK3-A2-Pad3)") (class "Default")
      (node (ref "OK3") (pin "3") (pinfunction "A2_3") (pintype "bidirectional"))
    )
    (net (code "186") (name "unconnected-(OK3-A3-Pad5)") (class "Default")
      (node (ref "OK3") (pin "5") (pinfunction "A3_5") (pintype "bidirectional"))
    )
    (net (code "187") (name "unconnected-(OK3-A4-Pad7)") (class "Default")
      (node (ref "OK3") (pin "7") (pinfunction "A4_7") (pintype "bidirectional"))
    )
    (net (code "188") (name "unconnected-(OK3-C2-Pad14)") (class "Default")
      (node (ref "OK3") (pin "14") (pinfunction "C2_14") (pintype "bidirectional"))
    )
    (net (code "189") (name "unconnected-(OK3-C3-Pad12)") (class "Default")
      (node (ref "OK3") (pin "12") (pinfunction "C3_12") (pintype "bidirectional"))
    )
    (net (code "190") (name "unconnected-(OK3-C4-Pad10)") (class "Default")
      (node (ref "OK3") (pin "10") (pinfunction "C4_10") (pintype "bidirectional"))
    )
    (net (code "191") (name "unconnected-(OK3-E2-Pad13)") (class "Default")
      (node (ref "OK3") (pin "13") (pinfunction "E2_13") (pintype "bidirectional"))
    )
    (net (code "192") (name "unconnected-(OK3-E3-Pad11)") (class "Default")
      (node (ref "OK3") (pin "11") (pinfunction "E3_11") (pintype "bidirectional"))
    )
    (net (code "193") (name "unconnected-(OK3-E4-Pad9)") (class "Default")
      (node (ref "OK3") (pin "9") (pinfunction "E4_9") (pintype "bidirectional"))
    )
    (net (code "194") (name "unconnected-(OK3-K2-Pad4)") (class "Default")
      (node (ref "OK3") (pin "4") (pinfunction "K2_4") (pintype "bidirectional"))
    )
    (net (code "195") (name "unconnected-(OK3-K3-Pad6)") (class "Default")
      (node (ref "OK3") (pin "6") (pinfunction "K3_6") (pintype "bidirectional"))
    )
    (net (code "196") (name "unconnected-(OK3-K4-Pad8)") (class "Default")
      (node (ref "OK3") (pin "8") (pinfunction "K4_8") (pintype "bidirectional"))
    )
    (net (code "197") (name "unconnected-(U1-ADC_IN0-Pad2)") (class "Default")
      (node (ref "U1") (pin "2") (pinfunction "ADC_IN0_2") (pintype "bidirectional"))
    )
    (net (code "198") (name "unconnected-(U1-ADC_IN1-Pad1)") (class "Default")
      (node (ref "U1") (pin "1") (pinfunction "ADC_IN1_1") (pintype "bidirectional"))
    )
    (net (code "199") (name "unconnected-(U1-ADC_IN2-Pad4)") (class "Default")
      (node (ref "U1") (pin "4") (pinfunction "ADC_IN2_4") (pintype "bidirectional"))
    )
    (net (code "200") (name "unconnected-(U1-ADC_IN3-Pad3)") (class "Default")
      (node (ref "U1") (pin "3") (pinfunction "ADC_IN3_3") (pintype "bidirectional"))
    )
    (net (code "201") (name "unconnected-(U1-ADC_IN4-Pad6)") (class "Default")
      (node (ref "U1") (pin "6") (pinfunction "ADC_IN4_6") (pintype "bidirectional"))
    )
    (net (code "202") (name "unconnected-(U1-ADC_IN7-Pad5)") (class "Default")
      (node (ref "U1") (pin "5") (pinfunction "ADC_IN7_5") (pintype "bidirectional"))
    )
    (net (code "203") (name "unconnected-(U1-AGND-Pad8)") (class "Default")
      (node (ref "U1") (pin "8") (pinfunction "AGND_8") (pintype "bidirectional"))
    )
    (net (code "204") (name "unconnected-(U1-CAN1_RX-Pad20)") (class "Default")
      (node (ref "U1") (pin "20") (pinfunction "CAN1_RX_20") (pintype "bidirectional"))
    )
    (net (code "205") (name "unconnected-(U1-CAN1_TX-Pad22)") (class "Default")
      (node (ref "U1") (pin "22") (pinfunction "CAN1_TX_22") (pintype "bidirectional"))
    )
    (net (code "206") (name "unconnected-(U1-ERX_JM-Pad44)") (class "Default")
      (node (ref "U1") (pin "44") (pinfunction "ERX_JM_44") (pintype "bidirectional"))
    )
    (net (code "207") (name "unconnected-(U1-ERX_JP-Pad43)") (class "Default")
      (node (ref "U1") (pin "43") (pinfunction "ERX_JP_43") (pintype "bidirectional"))
    )
    (net (code "208") (name "unconnected-(U1-ETX_JM-Pad46)") (class "Default")
      (node (ref "U1") (pin "46") (pinfunction "ETX_JM_46") (pintype "bidirectional"))
    )
    (net (code "209") (name "unconnected-(U1-ETX_JP-Pad45)") (class "Default")
      (node (ref "U1") (pin "45") (pinfunction "ETX_JP_45") (pintype "bidirectional"))
    )
    (net (code "210") (name "unconnected-(U1-IRQ2-Pad50)") (class "Default")
      (node (ref "U1") (pin "50") (pinfunction "IRQ2_50") (pintype "bidirectional"))
    )
    (net (code "211") (name "unconnected-(U1-IRQ3-Pad49)") (class "Default")
      (node (ref "U1") (pin "49") (pinfunction "IRQ3_49") (pintype "bidirectional"))
    )
    (net (code "212") (name "unconnected-(U1-IRQ7-Pad9)") (class "Default")
      (node (ref "U1") (pin "9") (pinfunction "IRQ7_9") (pintype "bidirectional"))
    )
    (net (code "213") (name "unconnected-(U1-LINKLED-Pad42)") (class "Default")
      (node (ref "U1") (pin "42") (pinfunction "LINKLED_42") (pintype "bidirectional"))
    )
    (net (code "214") (name "unconnected-(U1-OW_DAT-Pad12)") (class "Default")
      (node (ref "U1") (pin "12") (pinfunction "OW_DAT_12") (pintype "bidirectional"))
    )
    (net (code "215") (name "unconnected-(U1-RSTI-Pad11)") (class "Default")
      (node (ref "U1") (pin "11") (pinfunction "RSTI_11") (pintype "bidirectional"))
    )
    (net (code "216") (name "unconnected-(U1-SDHC_DAT3-Pad15)") (class "Default")
      (node (ref "U1") (pin "15") (pinfunction "SDHC_DAT3_15") (pintype "bidirectional"))
    )
    (net (code "217") (name "unconnected-(U1-SPEEDLED-Pad40)") (class "Default")
      (node (ref "U1") (pin "40") (pinfunction "SPEEDLED_40") (pintype "bidirectional"))
    )
    (net (code "218") (name "unconnected-(U1-T0IN-Pad19)") (class "Default")
      (node (ref "U1") (pin "19") (pinfunction "T0IN_19") (pintype "bidirectional"))
    )
    (net (code "219") (name "unconnected-(U1-T1IN-Pad21)") (class "Default")
      (node (ref "U1") (pin "21") (pinfunction "T1IN_21") (pintype "bidirectional"))
    )
    (net (code "220") (name "unconnected-(U1-T3IN-Pad25)") (class "Default")
      (node (ref "U1") (pin "25") (pinfunction "T3IN_25") (pintype "bidirectional"))
    )
    (net (code "221") (name "unconnected-(U1-UART0_CTS-Pad30)") (class "Default")
      (node (ref "U1") (pin "30") (pinfunction "UART0_CTS_30") (pintype "bidirectional"))
    )
    (net (code "222") (name "unconnected-(U1-UART0_RTS-Pad28)") (class "Default")
      (node (ref "U1") (pin "28") (pinfunction "UART0_RTS_28") (pintype "bidirectional"))
    )
    (net (code "223") (name "unconnected-(U1-UART0_RX-Pad24)") (class "Default")
      (node (ref "U1") (pin "24") (pinfunction "UART0_RX_24") (pintype "bidirectional"))
    )
    (net (code "224") (name "unconnected-(U1-UART0_TX-Pad26)") (class "Default")
      (node (ref "U1") (pin "26") (pinfunction "UART0_TX_26") (pintype "bidirectional"))
    )
    (net (code "225") (name "unconnected-(U1-UART2_CTS-Pad10)") (class "Default")
      (node (ref "U1") (pin "10") (pinfunction "UART2_CTS_10") (pintype "bidirectional"))
    )
    (net (code "226") (name "unconnected-(U1-UART2_RTS-Pad14)") (class "Default")
      (node (ref "U1") (pin "14") (pinfunction "UART2_RTS_14") (pintype "bidirectional"))
    )
    (net (code "227") (name "unconnected-(U1-UART2_RX-Pad13)") (class "Default")
      (node (ref "U1") (pin "13") (pinfunction "UART2_RX_13") (pintype "bidirectional"))
    )
    (net (code "228") (name "unconnected-(U1-UART2_TX-Pad16)") (class "Default")
      (node (ref "U1") (pin "16") (pinfunction "UART2_TX_16") (pintype "bidirectional"))
    )
    (net (code "229") (name "unconnected-(U1-USBO_DM-Pad51)") (class "Default")
      (node (ref "U1") (pin "51") (pinfunction "USBO_DM_51") (pintype "bidirectional"))
    )
    (net (code "230") (name "unconnected-(U1-USBO_DP-Pad52)") (class "Default")
      (node (ref "U1") (pin "52") (pinfunction "USBO_DP_52") (pintype "bidirectional"))
    )
    (net (code "231") (name "unconnected-(U1-VCC3VE-Pad41)") (class "Default")
      (node (ref "U1") (pin "41") (pinfunction "VCC3VE_41") (pintype "bidirectional"))
    )
    (net (code "232") (name "unconnected-(U1-VDDA_DAC_ADC-Pad7)") (class "Default")
      (node (ref "U1") (pin "7") (pinfunction "VDDA_DAC_ADC_7") (pintype "bidirectional"))
    )
    (net (code "233") (name "unconnected-(U2-COMP-PadB7)") (class "Default")
      (node (ref "U2") (pin "B7") (pinfunction "COMP_B7") (pintype "bidirectional"))
    )
    (net (code "234") (name "unconnected-(U2-EXTV_CC-PadF6)") (class "Default")
      (node (ref "U2") (pin "F6") (pinfunction "EXTV_CC_F6") (pintype "bidirectional"))
    )
    (net (code "235") (name "unconnected-(U2-PLLIN-PadB9)") (class "Default")
      (node (ref "U2") (pin "B9") (pinfunction "PLLIN_B9") (pintype "bidirectional"))
    )
    (net (code "236") (name "unconnected-(U2-SS-PadA6)") (class "Default")
      (node (ref "U2") (pin "A6") (pinfunction "SS_A6") (pintype "bidirectional"))
    )
    (net (code "237") (name "unconnected-(U2-STBYMD-PadA10)") (class "Default")
      (node (ref "U2") (pin "A10") (pinfunction "STBYMD_A10") (pintype "bidirectional"))
    )
    (net (code "238") (name "unconnected-(U3-TIMER1-Pad2)") (class "Default")
      (node (ref "U3") (pin "2") (pinfunction "TIMER1_2") (pintype "bidirectional"))
    )
    (net (code "239") (name "unconnected-(U3-TIMER2-Pad4)") (class "Default")
      (node (ref "U3") (pin "4") (pinfunction "TIMER2_4") (pintype "bidirectional"))
    )
    (net (code "240") (name "unconnected-(U3-TIMER3-Pad6)") (class "Default")
      (node (ref "U3") (pin "6") (pinfunction "TIMER3_6") (pintype "bidirectional"))
    )
    (net (code "241") (name "unconnected-(U3-TIMER4-Pad8)") (class "Default")
      (node (ref "U3") (pin "8") (pinfunction "TIMER4_8") (pintype "bidirectional"))
    )
    (net (code "242") (name "unconnected-(U4-TIMER1-Pad2)") (class "Default")
      (node (ref "U4") (pin "2") (pinfunction "TIMER1_2") (pintype "bidirectional"))
    )
    (net (code "243") (name "unconnected-(U4-TIMER2-Pad4)") (class "Default")
      (node (ref "U4") (pin "4") (pinfunction "TIMER2_4") (pintype "bidirectional"))
    )
    (net (code "244") (name "unconnected-(U4-TIMER3-Pad6)") (class "Default")
      (node (ref "U4") (pin "6") (pinfunction "TIMER3_6") (pintype "bidirectional"))
    )
    (net (code "245") (name "unconnected-(U4-TIMER4-Pad8)") (class "Default")
      (node (ref "U4") (pin "8") (pinfunction "TIMER4_8") (pintype "bidirectional"))
    )
  )
)
